# General_IO.net
KiCad netlist of a schematic drawn in EAGLE
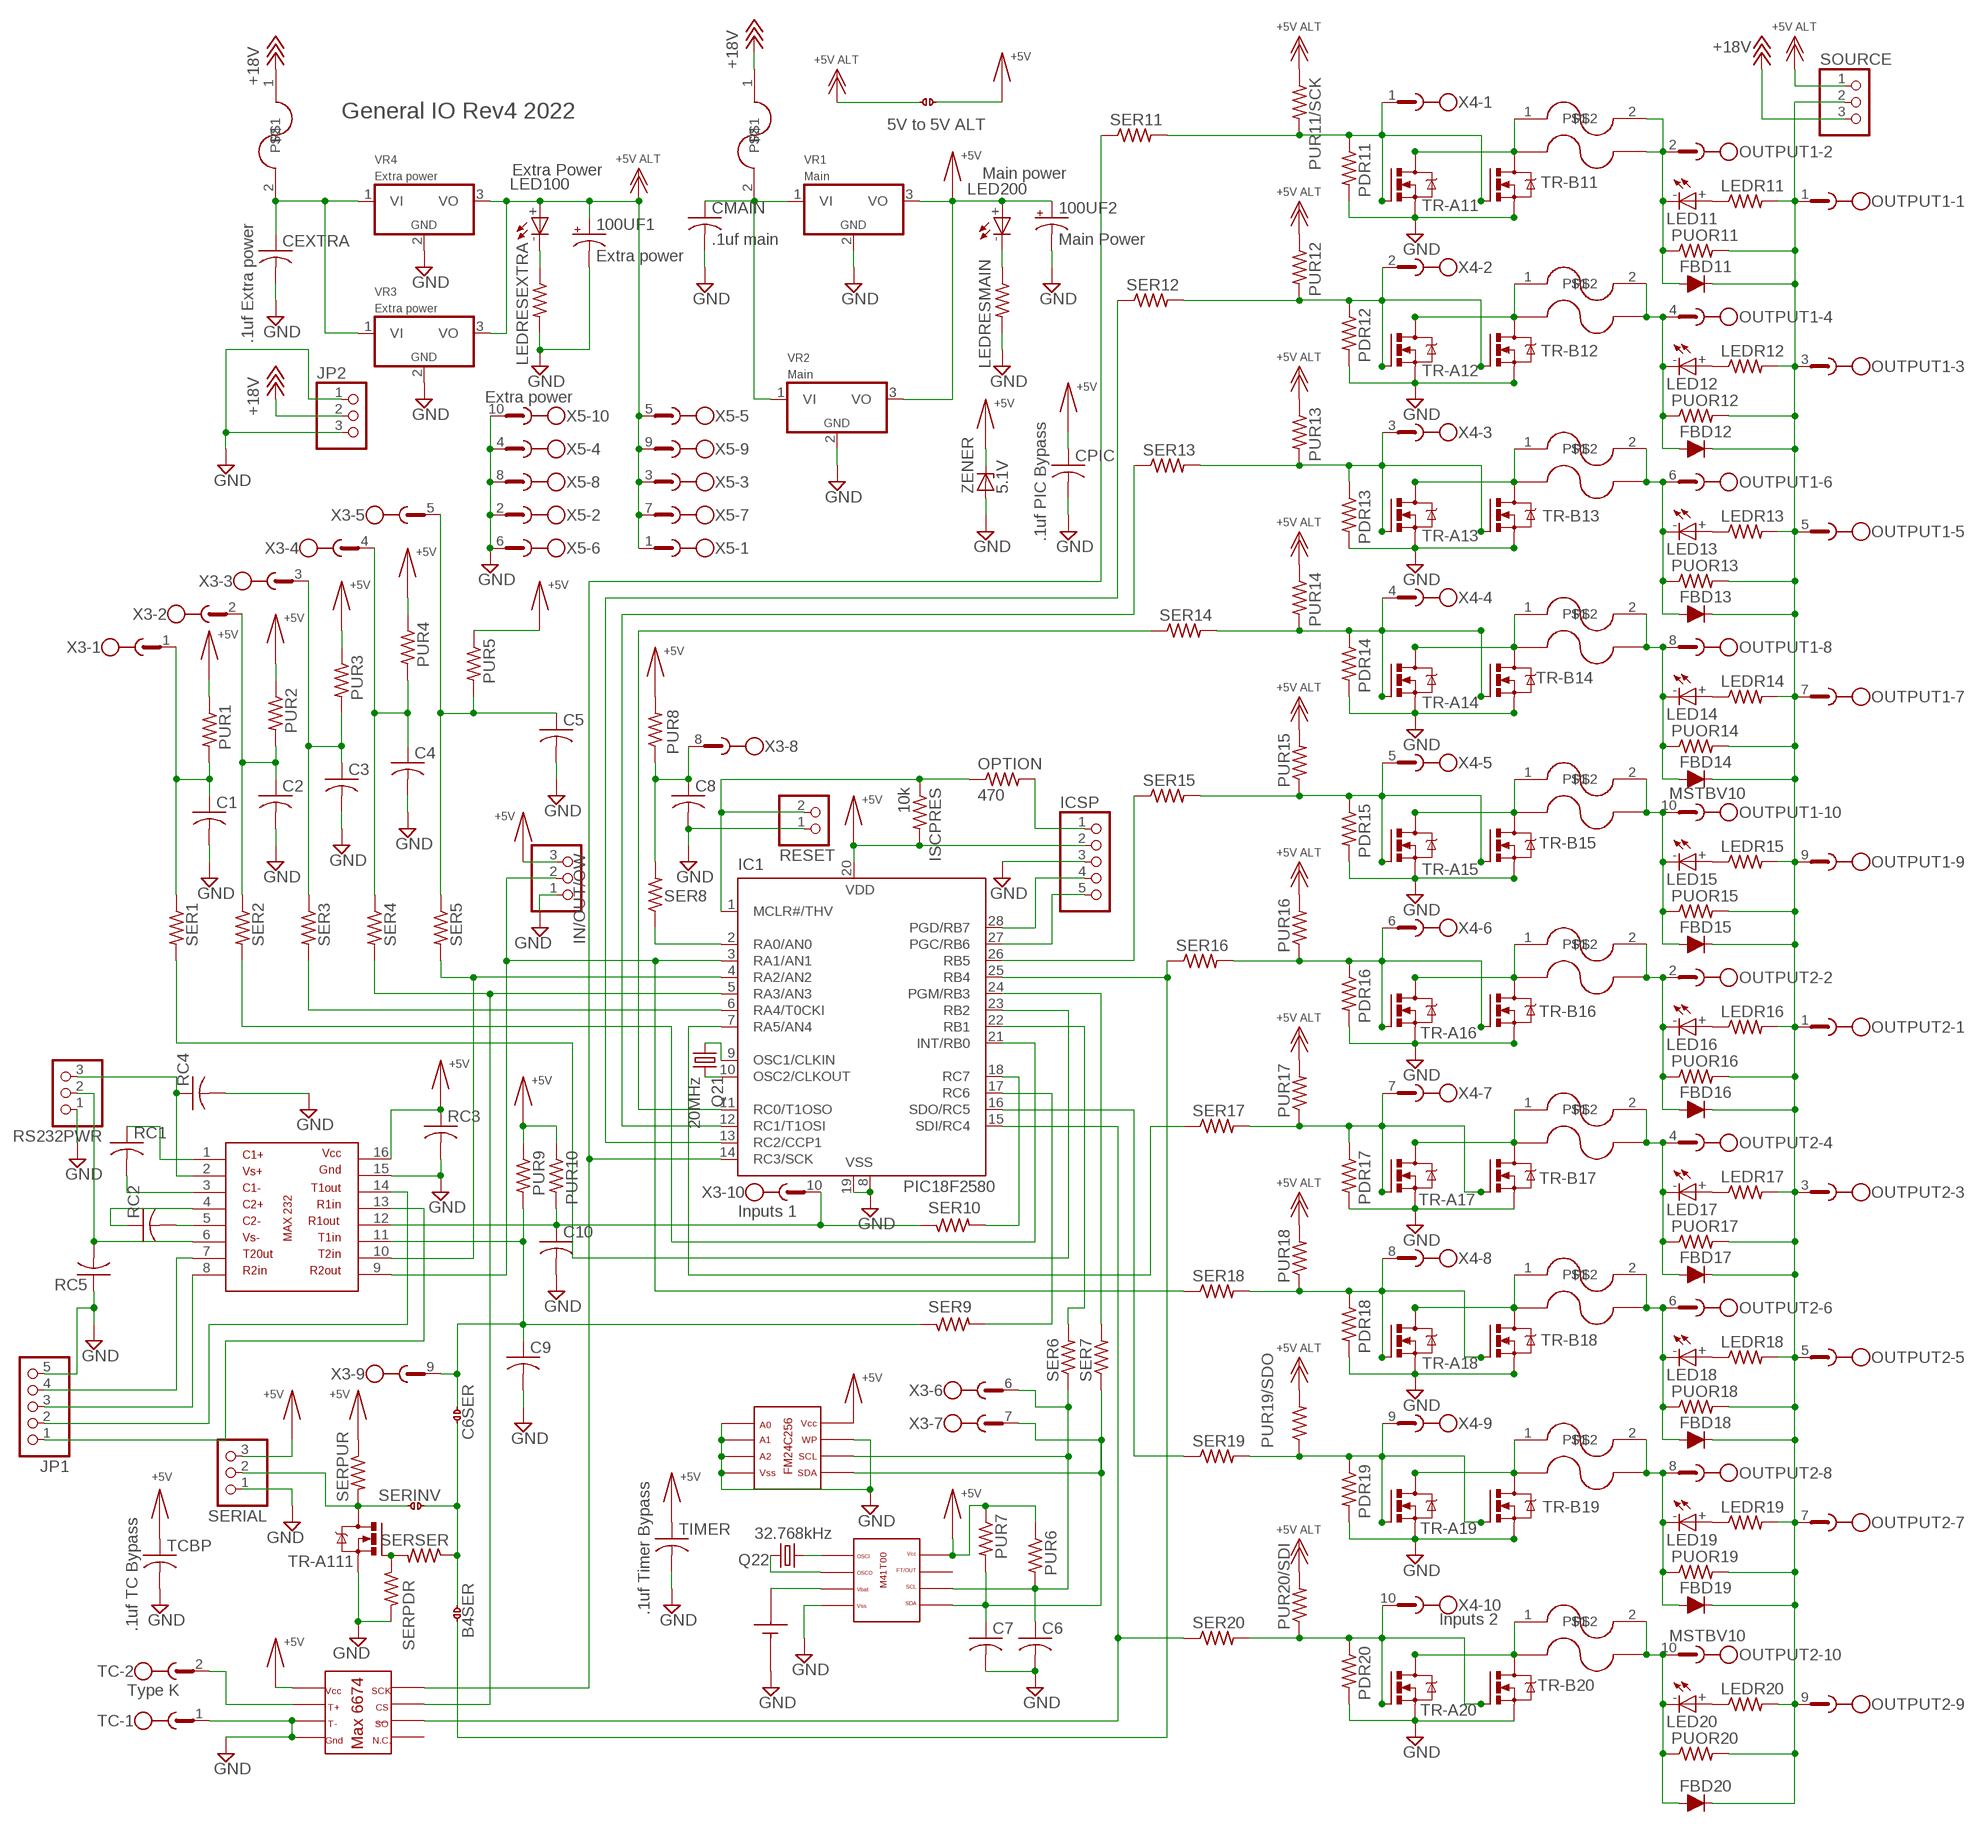
[diagram p0: schematic, sheet 1]

(export (version "E")
  (design (tool "Eeschema 10.0.6"))
  (components
    (comp (ref "100UF1")
      (value "Extra power")
      (footprint "eagle-import:PANASONIC_G")
      (libsource (lib "eagle-import") (part "CAPACITOR-ELECTROLYTICG"))
    )
    (comp (ref "100UF2")
      (value "Main Power")
      (footprint "eagle-import:PANASONIC_G")
      (libsource (lib "eagle-import") (part "CAPACITOR-ELECTROLYTICG"))
    )
    (comp (ref "BAT1")
      (value "BH-401")
      (footprint "eagle-import:BH-401")
      (libsource (lib "eagle-import") (part "BH-401"))
    )
    (comp (ref "C1")
      (value "CAPACITOR-NO-POLARITYC1210")
      (footprint "eagle-import:C1210")
      (libsource (lib "eagle-import") (part "CAPACITOR-NO-POLARITYC1210"))
    )
    (comp (ref "C2")
      (value "CAPACITOR-NO-POLARITYC1210")
      (footprint "eagle-import:C1210")
      (libsource (lib "eagle-import") (part "CAPACITOR-NO-POLARITYC1210"))
    )
    (comp (ref "C3")
      (value "CAPACITOR-NO-POLARITYC1210")
      (footprint "eagle-import:C1210")
      (libsource (lib "eagle-import") (part "CAPACITOR-NO-POLARITYC1210"))
    )
    (comp (ref "C4")
      (value "CAPACITOR-NO-POLARITYC1210")
      (footprint "eagle-import:C1210")
      (libsource (lib "eagle-import") (part "CAPACITOR-NO-POLARITYC1210"))
    )
    (comp (ref "C5")
      (value "CAPACITOR-NO-POLARITYC1210")
      (footprint "eagle-import:C1210")
      (libsource (lib "eagle-import") (part "CAPACITOR-NO-POLARITYC1210"))
    )
    (comp (ref "C6")
      (value "CAPACITOR-NO-POLARITYC1210")
      (footprint "eagle-import:C1210")
      (libsource (lib "eagle-import") (part "CAPACITOR-NO-POLARITYC1210"))
    )
    (comp (ref "C6SER")
      (value "SPLIT_PAD")
      (footprint "eagle-import:SPLIT_PAD")
      (libsource (lib "eagle-import") (part "SPLIT_PAD"))
    )
    (comp (ref "C7")
      (value "CAPACITOR-NO-POLARITYC1210")
      (footprint "eagle-import:C1210")
      (libsource (lib "eagle-import") (part "CAPACITOR-NO-POLARITYC1210"))
    )
    (comp (ref "C8")
      (value "CAPACITOR-NO-POLARITYC1210")
      (footprint "eagle-import:C1210")
      (libsource (lib "eagle-import") (part "CAPACITOR-NO-POLARITYC1210"))
    )
    (comp (ref "C9")
      (value "CAPACITOR-NO-POLARITYC1210")
      (footprint "eagle-import:C1210")
      (libsource (lib "eagle-import") (part "CAPACITOR-NO-POLARITYC1210"))
    )
    (comp (ref "C10")
      (value "CAPACITOR-NO-POLARITYC1210")
      (footprint "eagle-import:C1210")
      (libsource (lib "eagle-import") (part "CAPACITOR-NO-POLARITYC1210"))
    )
    (comp (ref "CEXTRA")
      (value ".1uf Extra power")
      (footprint "eagle-import:C1210")
      (libsource (lib "eagle-import") (part "CAPACITOR-NO-POLARITYC1210"))
    )
    (comp (ref "CMAIN")
      (value ".1uf main")
      (footprint "eagle-import:C1210")
      (libsource (lib "eagle-import") (part "CAPACITOR-NO-POLARITYC1210"))
    )
    (comp (ref "CPIC")
      (value ".1uf PIC Bypass")
      (footprint "eagle-import:C1210")
      (libsource (lib "eagle-import") (part "CAPACITOR-NO-POLARITYC1210"))
    )
    (comp (ref "FBD11")
      (value "D-FILL-SOD-87")
      (footprint "eagle-import:SOD87")
      (libsource (lib "eagle-import") (part "D-FILL-SOD-87"))
    )
    (comp (ref "FBD12")
      (value "D-FILL-SOD-87")
      (footprint "eagle-import:SOD87")
      (libsource (lib "eagle-import") (part "D-FILL-SOD-87"))
    )
    (comp (ref "FBD13")
      (value "D-FILL-SOD-87")
      (footprint "eagle-import:SOD87")
      (libsource (lib "eagle-import") (part "D-FILL-SOD-87"))
    )
    (comp (ref "FBD14")
      (value "D-FILL-SOD-87")
      (footprint "eagle-import:SOD87")
      (libsource (lib "eagle-import") (part "D-FILL-SOD-87"))
    )
    (comp (ref "FBD15")
      (value "D-FILL-SOD-87")
      (footprint "eagle-import:SOD87")
      (libsource (lib "eagle-import") (part "D-FILL-SOD-87"))
    )
    (comp (ref "FBD16")
      (value "D-FILL-SOD-87")
      (footprint "eagle-import:SOD87")
      (libsource (lib "eagle-import") (part "D-FILL-SOD-87"))
    )
    (comp (ref "FBD17")
      (value "D-FILL-SOD-87")
      (footprint "eagle-import:SOD87")
      (libsource (lib "eagle-import") (part "D-FILL-SOD-87"))
    )
    (comp (ref "FBD18")
      (value "D-FILL-SOD-87")
      (footprint "eagle-import:SOD87")
      (libsource (lib "eagle-import") (part "D-FILL-SOD-87"))
    )
    (comp (ref "FBD19")
      (value "D-FILL-SOD-87")
      (footprint "eagle-import:SOD87")
      (libsource (lib "eagle-import") (part "D-FILL-SOD-87"))
    )
    (comp (ref "FBD20")
      (value "D-FILL-SOD-87")
      (footprint "eagle-import:SOD87")
      (libsource (lib "eagle-import") (part "D-FILL-SOD-87"))
    )
    (comp (ref "FUSE9")
      (value "FUSE(SM)")
      (footprint "eagle-import:FUSE")
      (libsource (lib "eagle-import") (part "FUSE(SM)"))
    )
    (comp (ref "FUSE11")
      (value "FUSE(SM)")
      (footprint "eagle-import:FUSE")
      (libsource (lib "eagle-import") (part "FUSE(SM)"))
    )
    (comp (ref "FUSE12")
      (value "FUSE(SM)")
      (footprint "eagle-import:FUSE")
      (libsource (lib "eagle-import") (part "FUSE(SM)"))
    )
    (comp (ref "FUSE13")
      (value "FUSE(SM)")
      (footprint "eagle-import:FUSE")
      (libsource (lib "eagle-import") (part "FUSE(SM)"))
    )
    (comp (ref "FUSE14")
      (value "FUSE(SM)")
      (footprint "eagle-import:FUSE")
      (libsource (lib "eagle-import") (part "FUSE(SM)"))
    )
    (comp (ref "FUSE15")
      (value "FUSE(SM)")
      (footprint "eagle-import:FUSE")
      (libsource (lib "eagle-import") (part "FUSE(SM)"))
    )
    (comp (ref "FUSE16")
      (value "FUSE(SM)")
      (footprint "eagle-import:FUSE")
      (libsource (lib "eagle-import") (part "FUSE(SM)"))
    )
    (comp (ref "FUSE17")
      (value "FUSE(SM)")
      (footprint "eagle-import:FUSE")
      (libsource (lib "eagle-import") (part "FUSE(SM)"))
    )
    (comp (ref "FUSE18")
      (value "FUSE(SM)")
      (footprint "eagle-import:FUSE")
      (libsource (lib "eagle-import") (part "FUSE(SM)"))
    )
    (comp (ref "FUSE20")
      (value "FUSE(SM)")
      (footprint "eagle-import:FUSE")
      (libsource (lib "eagle-import") (part "FUSE(SM)"))
    )
    (comp (ref "IC1")
      (value "PIC18F2580")
      (footprint "eagle-import:SO-28W")
      (libsource (lib "eagle-import") (part "PIC16876SOF"))
    )
    (comp (ref "ICSP")
      (value "PINHD-1X5")
      (footprint "eagle-import:1X05")
      (libsource (lib "eagle-import") (part "PINHD-1X5"))
    )
    (comp (ref "IN/OUT/OW")
      (value "PINHD-1X3")
      (footprint "eagle-import:1X03")
      (libsource (lib "eagle-import") (part "PINHD-1X3"))
    )
    (comp (ref "ISCPRES")
      (value "10k")
      (footprint "eagle-import:M1406")
      (libsource (lib "eagle-import") (part "RESISITORM1406"))
    )
    (comp (ref "JP1")
      (value "PINHD-1X5")
      (footprint "eagle-import:1X05")
      (libsource (lib "eagle-import") (part "PINHD-1X5"))
    )
    (comp (ref "JP2")
      (value "PINHD-1X3")
      (footprint "eagle-import:1X03")
      (libsource (lib "eagle-import") (part "PINHD-1X3"))
    )
    (comp (ref "LED11")
      (value "LED")
      (footprint "eagle-import:1206")
      (libsource (lib "eagle-import") (part "LED"))
    )
    (comp (ref "LED12")
      (value "LED")
      (footprint "eagle-import:1206")
      (libsource (lib "eagle-import") (part "LED"))
    )
    (comp (ref "LED13")
      (value "LED")
      (footprint "eagle-import:1206")
      (libsource (lib "eagle-import") (part "LED"))
    )
    (comp (ref "LED14")
      (value "LED")
      (footprint "eagle-import:1206")
      (libsource (lib "eagle-import") (part "LED"))
    )
    (comp (ref "LED15")
      (value "LED")
      (footprint "eagle-import:1206")
      (libsource (lib "eagle-import") (part "LED"))
    )
    (comp (ref "LED16")
      (value "LED")
      (footprint "eagle-import:1206")
      (libsource (lib "eagle-import") (part "LED"))
    )
    (comp (ref "LED17")
      (value "LED")
      (footprint "eagle-import:1206")
      (libsource (lib "eagle-import") (part "LED"))
    )
    (comp (ref "LED18")
      (value "LED")
      (footprint "eagle-import:1206")
      (libsource (lib "eagle-import") (part "LED"))
    )
    (comp (ref "LED19")
      (value "LED")
      (footprint "eagle-import:1206")
      (libsource (lib "eagle-import") (part "LED"))
    )
    (comp (ref "LED20")
      (value "LED")
      (footprint "eagle-import:1206")
      (libsource (lib "eagle-import") (part "LED"))
    )
    (comp (ref "LED100")
      (value "Extra Power")
      (footprint "eagle-import:1206")
      (libsource (lib "eagle-import") (part "LED"))
    )
    (comp (ref "LED200")
      (value "Main power")
      (footprint "eagle-import:1206")
      (libsource (lib "eagle-import") (part "LED"))
    )
    (comp (ref "LEDR11")
      (value "RESISITORM1406")
      (footprint "eagle-import:M1406")
      (libsource (lib "eagle-import") (part "RESISITORM1406"))
    )
    (comp (ref "LEDR12")
      (value "RESISITORM1406")
      (footprint "eagle-import:M1406")
      (libsource (lib "eagle-import") (part "RESISITORM1406"))
    )
    (comp (ref "LEDR13")
      (value "RESISITORM1406")
      (footprint "eagle-import:M1406")
      (libsource (lib "eagle-import") (part "RESISITORM1406"))
    )
    (comp (ref "LEDR14")
      (value "RESISITORM1406")
      (footprint "eagle-import:M1406")
      (libsource (lib "eagle-import") (part "RESISITORM1406"))
    )
    (comp (ref "LEDR15")
      (value "RESISITORM1406")
      (footprint "eagle-import:M1406")
      (libsource (lib "eagle-import") (part "RESISITORM1406"))
    )
    (comp (ref "LEDR16")
      (value "RESISITORM1406")
      (footprint "eagle-import:M1406")
      (libsource (lib "eagle-import") (part "RESISITORM1406"))
    )
    (comp (ref "LEDR17")
      (value "RESISITORM1406")
      (footprint "eagle-import:M1406")
      (libsource (lib "eagle-import") (part "RESISITORM1406"))
    )
    (comp (ref "LEDR18")
      (value "RESISITORM1406")
      (footprint "eagle-import:M1406")
      (libsource (lib "eagle-import") (part "RESISITORM1406"))
    )
    (comp (ref "LEDR19")
      (value "RESISITORM1406")
      (footprint "eagle-import:M1406")
      (libsource (lib "eagle-import") (part "RESISITORM1406"))
    )
    (comp (ref "LEDR20")
      (value "RESISITORM1406")
      (footprint "eagle-import:M1406")
      (libsource (lib "eagle-import") (part "RESISITORM1406"))
    )
    (comp (ref "LEDRESEXTRA")
      (value "RESISITORR1210")
      (footprint "eagle-import:R1210")
      (libsource (lib "eagle-import") (part "RESISITORR1210"))
    )
    (comp (ref "LEDRESMAIN")
      (value "RESISITORR1210")
      (footprint "eagle-import:R1210")
      (libsource (lib "eagle-import") (part "RESISITORR1210"))
    )
    (comp (ref "OPTION")
      (value "470")
      (footprint "eagle-import:M1406")
      (libsource (lib "eagle-import") (part "RESISITORM1406"))
    )
    (comp (ref "OUTPUT1")
      (value "MSTBV10")
      (footprint "eagle-import:MSTBV10")
      (libsource (lib "eagle-import") (part "MSTBV10"))
    )
    (comp (ref "OUTPUT2")
      (value "MSTBV10")
      (footprint "eagle-import:MSTBV10")
      (libsource (lib "eagle-import") (part "MSTBV10"))
    )
    (comp (ref "PDR11")
      (value "RESISITORM1406")
      (footprint "eagle-import:M1406")
      (libsource (lib "eagle-import") (part "RESISITORM1406"))
    )
    (comp (ref "PDR12")
      (value "RESISITORM1406")
      (footprint "eagle-import:M1406")
      (libsource (lib "eagle-import") (part "RESISITORM1406"))
    )
    (comp (ref "PDR13")
      (value "RESISITORM1406")
      (footprint "eagle-import:M1406")
      (libsource (lib "eagle-import") (part "RESISITORM1406"))
    )
    (comp (ref "PDR14")
      (value "RESISITORM1406")
      (footprint "eagle-import:M1406")
      (libsource (lib "eagle-import") (part "RESISITORM1406"))
    )
    (comp (ref "PDR15")
      (value "RESISITORM1406")
      (footprint "eagle-import:M1406")
      (libsource (lib "eagle-import") (part "RESISITORM1406"))
    )
    (comp (ref "PDR16")
      (value "RESISITORM1406")
      (footprint "eagle-import:M1406")
      (libsource (lib "eagle-import") (part "RESISITORM1406"))
    )
    (comp (ref "PDR17")
      (value "RESISITORM1406")
      (footprint "eagle-import:M1406")
      (libsource (lib "eagle-import") (part "RESISITORM1406"))
    )
    (comp (ref "PDR18")
      (value "RESISITORM1406")
      (footprint "eagle-import:M1406")
      (libsource (lib "eagle-import") (part "RESISITORM1406"))
    )
    (comp (ref "PDR19")
      (value "RESISITORM1406")
      (footprint "eagle-import:M1406")
      (libsource (lib "eagle-import") (part "RESISITORM1406"))
    )
    (comp (ref "PDR20")
      (value "RESISITORM1406")
      (footprint "eagle-import:M1406")
      (libsource (lib "eagle-import") (part "RESISITORM1406"))
    )
    (comp (ref "POLYFUSE11")
      (value "POLYFUSE")
      (footprint "eagle-import:0204_5")
      (libsource (lib "eagle-import") (part "POLYFUSE"))
    )
    (comp (ref "POLYFUSE12")
      (value "POLYFUSE")
      (footprint "eagle-import:0204_5")
      (libsource (lib "eagle-import") (part "POLYFUSE"))
    )
    (comp (ref "POLYFUSE13")
      (value "POLYFUSE")
      (footprint "eagle-import:0204_5")
      (libsource (lib "eagle-import") (part "POLYFUSE"))
    )
    (comp (ref "POLYFUSE14")
      (value "POLYFUSE")
      (footprint "eagle-import:0204_5")
      (libsource (lib "eagle-import") (part "POLYFUSE"))
    )
    (comp (ref "POLYFUSE15")
      (value "POLYFUSE")
      (footprint "eagle-import:0204_5")
      (libsource (lib "eagle-import") (part "POLYFUSE"))
    )
    (comp (ref "POLYFUSE16")
      (value "POLYFUSE")
      (footprint "eagle-import:0204_5")
      (libsource (lib "eagle-import") (part "POLYFUSE"))
    )
    (comp (ref "POLYFUSE17")
      (value "POLYFUSE")
      (footprint "eagle-import:0204_5")
      (libsource (lib "eagle-import") (part "POLYFUSE"))
    )
    (comp (ref "POLYFUSE18")
      (value "POLYFUSE")
      (footprint "eagle-import:0204_5")
      (libsource (lib "eagle-import") (part "POLYFUSE"))
    )
    (comp (ref "POLYFUSE19")
      (value "POLYFUSE")
      (footprint "eagle-import:0204_5")
      (libsource (lib "eagle-import") (part "POLYFUSE"))
    )
    (comp (ref "POLYFUSE20")
      (value "POLYFUSE")
      (footprint "eagle-import:0204_5")
      (libsource (lib "eagle-import") (part "POLYFUSE"))
    )
    (comp (ref "POLYFUSE100")
      (value "Extra Power")
      (footprint "eagle-import:0204_5")
      (libsource (lib "eagle-import") (part "POLYFUSE"))
    )
    (comp (ref "POLYFUSE200")
      (value "Main power")
      (footprint "eagle-import:0204_5")
      (libsource (lib "eagle-import") (part "POLYFUSE"))
    )
    (comp (ref "PUOR11")
      (value "RESISITORM1406")
      (footprint "eagle-import:M1406")
      (libsource (lib "eagle-import") (part "RESISITORM1406"))
    )
    (comp (ref "PUOR12")
      (value "RESISITORM1406")
      (footprint "eagle-import:M1406")
      (libsource (lib "eagle-import") (part "RESISITORM1406"))
    )
    (comp (ref "PUOR13")
      (value "RESISITORM1406")
      (footprint "eagle-import:M1406")
      (libsource (lib "eagle-import") (part "RESISITORM1406"))
    )
    (comp (ref "PUOR14")
      (value "RESISITORM1406")
      (footprint "eagle-import:M1406")
      (libsource (lib "eagle-import") (part "RESISITORM1406"))
    )
    (comp (ref "PUOR15")
      (value "RESISITORM1406")
      (footprint "eagle-import:M1406")
      (libsource (lib "eagle-import") (part "RESISITORM1406"))
    )
    (comp (ref "PUOR16")
      (value "RESISITORM1406")
      (footprint "eagle-import:M1406")
      (libsource (lib "eagle-import") (part "RESISITORM1406"))
    )
    (comp (ref "PUOR17")
      (value "RESISITORM1406")
      (footprint "eagle-import:M1406")
      (libsource (lib "eagle-import") (part "RESISITORM1406"))
    )
    (comp (ref "PUOR18")
      (value "RESISITORM1406")
      (footprint "eagle-import:M1406")
      (libsource (lib "eagle-import") (part "RESISITORM1406"))
    )
    (comp (ref "PUOR19")
      (value "RESISITORM1406")
      (footprint "eagle-import:M1406")
      (libsource (lib "eagle-import") (part "RESISITORM1406"))
    )
    (comp (ref "PUOR20")
      (value "RESISITORM1406")
      (footprint "eagle-import:M1406")
      (libsource (lib "eagle-import") (part "RESISITORM1406"))
    )
    (comp (ref "PUR1")
      (value "RESISITORM1406")
      (footprint "eagle-import:M1406")
      (libsource (lib "eagle-import") (part "RESISITORM1406"))
    )
    (comp (ref "PUR2")
      (value "RESISITORM1406")
      (footprint "eagle-import:M1406")
      (libsource (lib "eagle-import") (part "RESISITORM1406"))
    )
    (comp (ref "PUR3")
      (value "RESISITORM1406")
      (footprint "eagle-import:M1406")
      (libsource (lib "eagle-import") (part "RESISITORM1406"))
    )
    (comp (ref "PUR4")
      (value "RESISITORM1406")
      (footprint "eagle-import:M1406")
      (libsource (lib "eagle-import") (part "RESISITORM1406"))
    )
    (comp (ref "PUR5")
      (value "RESISITORM1406")
      (footprint "eagle-import:M1406")
      (libsource (lib "eagle-import") (part "RESISITORM1406"))
    )
    (comp (ref "PUR6")
      (value "RESISITORM1406")
      (footprint "eagle-import:M1406")
      (libsource (lib "eagle-import") (part "RESISITORM1406"))
    )
    (comp (ref "PUR7")
      (value "RESISITORM1406")
      (footprint "eagle-import:M1406")
      (libsource (lib "eagle-import") (part "RESISITORM1406"))
    )
    (comp (ref "PUR8")
      (value "RESISITORM1406")
      (footprint "eagle-import:M1406")
      (libsource (lib "eagle-import") (part "RESISITORM1406"))
    )
    (comp (ref "PUR9")
      (value "RESISITORM1406")
      (footprint "eagle-import:M1406")
      (libsource (lib "eagle-import") (part "RESISITORM1406"))
    )
    (comp (ref "PUR10")
      (value "RESISITORM1406")
      (footprint "eagle-import:M1406")
      (libsource (lib "eagle-import") (part "RESISITORM1406"))
    )
    (comp (ref "PUR11/SCK")
      (value "RESISITORM1406")
      (footprint "eagle-import:M1406")
      (libsource (lib "eagle-import") (part "RESISITORM1406"))
    )
    (comp (ref "PUR12")
      (value "RESISITORM1406")
      (footprint "eagle-import:M1406")
      (libsource (lib "eagle-import") (part "RESISITORM1406"))
    )
    (comp (ref "PUR13")
      (value "RESISITORM1406")
      (footprint "eagle-import:M1406")
      (libsource (lib "eagle-import") (part "RESISITORM1406"))
    )
    (comp (ref "PUR14")
      (value "RESISITORM1406")
      (footprint "eagle-import:M1406")
      (libsource (lib "eagle-import") (part "RESISITORM1406"))
    )
    (comp (ref "PUR15")
      (value "RESISITORM1406")
      (footprint "eagle-import:M1406")
      (libsource (lib "eagle-import") (part "RESISITORM1406"))
    )
    (comp (ref "PUR16")
      (value "RESISITORM1406")
      (footprint "eagle-import:M1406")
      (libsource (lib "eagle-import") (part "RESISITORM1406"))
    )
    (comp (ref "PUR17")
      (value "RESISITORM1406")
      (footprint "eagle-import:M1406")
      (libsource (lib "eagle-import") (part "RESISITORM1406"))
    )
    (comp (ref "PUR18")
      (value "RESISITORM1406")
      (footprint "eagle-import:M1406")
      (libsource (lib "eagle-import") (part "RESISITORM1406"))
    )
    (comp (ref "PUR19/SDO")
      (value "RESISITORM1406")
      (footprint "eagle-import:M1406")
      (libsource (lib "eagle-import") (part "RESISITORM1406"))
    )
    (comp (ref "PUR20/SDI")
      (value "RESISITORM1406")
      (footprint "eagle-import:M1406")
      (libsource (lib "eagle-import") (part "RESISITORM1406"))
    )
    (comp (ref "Q21")
      (value "20MHz")
      (footprint "eagle-import:SM49")
      (libsource (lib "eagle-import") (part "CRYSTALSM49"))
    )
    (comp (ref "Q22")
      (value "32.768kHz")
      (footprint "eagle-import:TC26H")
      (libsource (lib "eagle-import") (part "CRYSTALTC26H"))
    )
    (comp (ref "RC1")
      (value "CAPACITOR-NO-POLARITYC1210")
      (footprint "eagle-import:C1210")
      (libsource (lib "eagle-import") (part "CAPACITOR-NO-POLARITYC1210"))
    )
    (comp (ref "RC2")
      (value "CAPACITOR-NO-POLARITYC1210")
      (footprint "eagle-import:C1210")
      (libsource (lib "eagle-import") (part "CAPACITOR-NO-POLARITYC1210"))
    )
    (comp (ref "RC3")
      (value "CAPACITOR-NO-POLARITYC1210")
      (footprint "eagle-import:C1210")
      (libsource (lib "eagle-import") (part "CAPACITOR-NO-POLARITYC1210"))
    )
    (comp (ref "RC4")
      (value "CAPACITOR-NO-POLARITYC1210")
      (footprint "eagle-import:C1210")
      (libsource (lib "eagle-import") (part "CAPACITOR-NO-POLARITYC1210"))
    )
    (comp (ref "RC5")
      (value "CAPACITOR-NO-POLARITYC1210")
      (footprint "eagle-import:C1210")
      (libsource (lib "eagle-import") (part "CAPACITOR-NO-POLARITYC1210"))
    )
    (comp (ref "RESET")
      (value "PINHD-1X2")
      (footprint "eagle-import:1X02")
      (libsource (lib "eagle-import") (part "PINHD-1X2"))
    )
    (comp (ref "RS232PWR")
      (value "PINHD-1X3")
      (footprint "eagle-import:1X03")
      (libsource (lib "eagle-import") (part "PINHD-1X3"))
    )
    (comp (ref "SER1")
      (value "RESISITORM1406")
      (footprint "eagle-import:M1406")
      (libsource (lib "eagle-import") (part "RESISITORM1406"))
    )
    (comp (ref "SER2")
      (value "RESISITORM1406")
      (footprint "eagle-import:M1406")
      (libsource (lib "eagle-import") (part "RESISITORM1406"))
    )
    (comp (ref "SER3")
      (value "RESISITORM1406")
      (footprint "eagle-import:M1406")
      (libsource (lib "eagle-import") (part "RESISITORM1406"))
    )
    (comp (ref "SER4")
      (value "RESISITORM1406")
      (footprint "eagle-import:M1406")
      (libsource (lib "eagle-import") (part "RESISITORM1406"))
    )
    (comp (ref "SER5")
      (value "RESISITORM1406")
      (footprint "eagle-import:M1406")
      (libsource (lib "eagle-import") (part "RESISITORM1406"))
    )
    (comp (ref "SER6")
      (value "RESISITORM1406")
      (footprint "eagle-import:M1406")
      (libsource (lib "eagle-import") (part "RESISITORM1406"))
    )
    (comp (ref "SER7")
      (value "RESISITORM1406")
      (footprint "eagle-import:M1406")
      (libsource (lib "eagle-import") (part "RESISITORM1406"))
    )
    (comp (ref "SER8")
      (value "RESISITORM1406")
      (footprint "eagle-import:M1406")
      (libsource (lib "eagle-import") (part "RESISITORM1406"))
    )
    (comp (ref "SER9")
      (value "RESISITORM1406")
      (footprint "eagle-import:M1406")
      (libsource (lib "eagle-import") (part "RESISITORM1406"))
    )
    (comp (ref "SER10")
      (value "RESISITORM1406")
      (footprint "eagle-import:M1406")
      (libsource (lib "eagle-import") (part "RESISITORM1406"))
    )
    (comp (ref "SER11")
      (value "RESISITORM1406")
      (footprint "eagle-import:M1406")
      (libsource (lib "eagle-import") (part "RESISITORM1406"))
    )
    (comp (ref "SER12")
      (value "RESISITORM1406")
      (footprint "eagle-import:M1406")
      (libsource (lib "eagle-import") (part "RESISITORM1406"))
    )
    (comp (ref "SER13")
      (value "RESISITORM1406")
      (footprint "eagle-import:M1406")
      (libsource (lib "eagle-import") (part "RESISITORM1406"))
    )
    (comp (ref "SER14")
      (value "RESISITORM1406")
      (footprint "eagle-import:M1406")
      (libsource (lib "eagle-import") (part "RESISITORM1406"))
    )
    (comp (ref "SER15")
      (value "RESISITORM1406")
      (footprint "eagle-import:M1406")
      (libsource (lib "eagle-import") (part "RESISITORM1406"))
    )
    (comp (ref "SER16")
      (value "RESISITORM1406")
      (footprint "eagle-import:M1406")
      (libsource (lib "eagle-import") (part "RESISITORM1406"))
    )
    (comp (ref "SER17")
      (value "RESISITORM1406")
      (footprint "eagle-import:M1406")
      (libsource (lib "eagle-import") (part "RESISITORM1406"))
    )
    (comp (ref "SER18")
      (value "RESISITORM1406")
      (footprint "eagle-import:M1406")
      (libsource (lib "eagle-import") (part "RESISITORM1406"))
    )
    (comp (ref "SER19")
      (value "RESISITORM1406")
      (footprint "eagle-import:M1406")
      (libsource (lib "eagle-import") (part "RESISITORM1406"))
    )
    (comp (ref "SER20")
      (value "RESISITORM1406")
      (footprint "eagle-import:M1406")
      (libsource (lib "eagle-import") (part "RESISITORM1406"))
    )
    (comp (ref "SERIAL")
      (value "PINHD-1X3")
      (footprint "eagle-import:1X03")
      (libsource (lib "eagle-import") (part "PINHD-1X3"))
    )
    (comp (ref "SERPDR")
      (value "RESISITORM1406")
      (footprint "eagle-import:M1406")
      (libsource (lib "eagle-import") (part "RESISITORM1406"))
    )
    (comp (ref "SERPUR")
      (value "RESISITORM1406")
      (footprint "eagle-import:M1406")
      (libsource (lib "eagle-import") (part "RESISITORM1406"))
    )
    (comp (ref "SERSER")
      (value "RESISITORM1406")
      (footprint "eagle-import:M1406")
      (libsource (lib "eagle-import") (part "RESISITORM1406"))
    )
    (comp (ref "SOURCE")
      (value "PINHD-1X3")
      (footprint "eagle-import:1X03")
      (libsource (lib "eagle-import") (part "PINHD-1X3"))
    )
    (comp (ref "TC")
      (value "Type K")
      (footprint "eagle-import:MSTBV2")
      (libsource (lib "eagle-import") (part "MST2V"))
    )
    (comp (ref "TCBP")
      (value ".1uf TC Bypass")
      (footprint "eagle-import:C1210")
      (libsource (lib "eagle-import") (part "CAPACITOR-NO-POLARITYC1210"))
    )
    (comp (ref "TIMER")
      (value ".1uf Timer Bypass")
      (footprint "eagle-import:C1210")
      (libsource (lib "eagle-import") (part "CAPACITOR-NO-POLARITYC1210"))
    )
    (comp (ref "TR-A11")
      (value "ZXMN10A08GSOT223")
      (footprint "eagle-import:SOT223R_INFINEON")
      (libsource (lib "eagle-import") (part "ZXMN10A08GSOT223"))
    )
    (comp (ref "TR-A12")
      (value "ZXMN10A08GSOT223")
      (footprint "eagle-import:SOT223R_INFINEON")
      (libsource (lib "eagle-import") (part "ZXMN10A08GSOT223"))
    )
    (comp (ref "TR-A13")
      (value "ZXMN10A08GSOT223")
      (footprint "eagle-import:SOT223R_INFINEON")
      (libsource (lib "eagle-import") (part "ZXMN10A08GSOT223"))
    )
    (comp (ref "TR-A14")
      (value "ZXMN10A08GSOT223")
      (footprint "eagle-import:SOT223R_INFINEON")
      (libsource (lib "eagle-import") (part "ZXMN10A08GSOT223"))
    )
    (comp (ref "TR-A15")
      (value "ZXMN10A08GSOT223")
      (footprint "eagle-import:SOT223R_INFINEON")
      (libsource (lib "eagle-import") (part "ZXMN10A08GSOT223"))
    )
    (comp (ref "TR-A16")
      (value "ZXMN10A08GSOT223")
      (footprint "eagle-import:SOT223R_INFINEON")
      (libsource (lib "eagle-import") (part "ZXMN10A08GSOT223"))
    )
    (comp (ref "TR-A17")
      (value "ZXMN10A08GSOT223")
      (footprint "eagle-import:SOT223R_INFINEON")
      (libsource (lib "eagle-import") (part "ZXMN10A08GSOT223"))
    )
    (comp (ref "TR-A18")
      (value "ZXMN10A08GSOT223")
      (footprint "eagle-import:SOT223R_INFINEON")
      (libsource (lib "eagle-import") (part "ZXMN10A08GSOT223"))
    )
    (comp (ref "TR-A19")
      (value "ZXMN10A08GSOT223")
      (footprint "eagle-import:SOT223R_INFINEON")
      (libsource (lib "eagle-import") (part "ZXMN10A08GSOT223"))
    )
    (comp (ref "TR-A20")
      (value "ZXMN10A08GSOT223")
      (footprint "eagle-import:SOT223R_INFINEON")
      (libsource (lib "eagle-import") (part "ZXMN10A08GSOT223"))
    )
    (comp (ref "TR-A111")
      (value "ZXMN10A08GSOT223")
      (footprint "eagle-import:SOT223R_INFINEON")
      (libsource (lib "eagle-import") (part "ZXMN10A08GSOT223"))
    )
    (comp (ref "TR-B11")
      (value "ZXMN10A08G")
      (footprint "eagle-import:TO220BV")
      (libsource (lib "eagle-import") (part "ZXMN10A08G"))
    )
    (comp (ref "TR-B12")
      (value "ZXMN10A08G")
      (footprint "eagle-import:TO220BV")
      (libsource (lib "eagle-import") (part "ZXMN10A08G"))
    )
    (comp (ref "TR-B13")
      (value "ZXMN10A08G")
      (footprint "eagle-import:TO220BV")
      (libsource (lib "eagle-import") (part "ZXMN10A08G"))
    )
    (comp (ref "TR-B14")
      (value "ZXMN10A08G")
      (footprint "eagle-import:TO220BV")
      (libsource (lib "eagle-import") (part "ZXMN10A08G"))
    )
    (comp (ref "TR-B15")
      (value "ZXMN10A08G")
      (footprint "eagle-import:TO220BV")
      (libsource (lib "eagle-import") (part "ZXMN10A08G"))
    )
    (comp (ref "TR-B16")
      (value "ZXMN10A08G")
      (footprint "eagle-import:TO220BV")
      (libsource (lib "eagle-import") (part "ZXMN10A08G"))
    )
    (comp (ref "TR-B17")
      (value "ZXMN10A08G")
      (footprint "eagle-import:TO220BV")
      (libsource (lib "eagle-import") (part "ZXMN10A08G"))
    )
    (comp (ref "TR-B18")
      (value "ZXMN10A08G")
      (footprint "eagle-import:TO220BV")
      (libsource (lib "eagle-import") (part "ZXMN10A08G"))
    )
    (comp (ref "TR-B19")
      (value "ZXMN10A08G")
      (footprint "eagle-import:TO220BV")
      (libsource (lib "eagle-import") (part "ZXMN10A08G"))
    )
    (comp (ref "TR-B20")
      (value "ZXMN10A08G")
      (footprint "eagle-import:TO220BV")
      (libsource (lib "eagle-import") (part "ZXMN10A08G"))
    )
    (comp (ref "U$1")
      (value "MAX232")
      (footprint "eagle-import:SO16")
      (libsource (lib "eagle-import") (part "MAX232"))
    )
    (comp (ref "U$2")
      (value "MAX6674")
      (footprint "eagle-import:SO08")
      (libsource (lib "eagle-import") (part "MAX6674"))
    )
    (comp (ref "U$4")
      (value "M41T00TIMER-I2C")
      (footprint "eagle-import:SO08")
      (libsource (lib "eagle-import") (part "M41T00TIMER-I2C"))
    )
    (comp (ref "U$18")
      (value "FM24C256")
      (footprint "eagle-import:SO08")
      (libsource (lib "eagle-import") (part "FM24C256"))
    )
    (comp (ref "U$21")
      (value "SPLIT_PAD")
      (footprint "eagle-import:SPLIT_PAD")
      (libsource (lib "eagle-import") (part "SPLIT_PAD"))
    )
    (comp (ref "U$23")
      (value "SPLIT_PAD")
      (footprint "eagle-import:SPLIT_PAD")
      (libsource (lib "eagle-import") (part "SPLIT_PAD"))
    )
    (comp (ref "U$24")
      (value "SPLIT_PAD")
      (footprint "eagle-import:SPLIT_PAD")
      (libsource (lib "eagle-import") (part "SPLIT_PAD"))
    )
    (comp (ref "VR1")
      (value "Main")
      (footprint "eagle-import:TO220S")
      (libsource (lib "eagle-import") (part "VOLTAGE-REGULATOR"))
    )
    (comp (ref "VR2")
      (value "Main")
      (footprint "eagle-import:SOT223R_INFINEON")
      (libsource (lib "eagle-import") (part "VOLTAGE-REGULATORSO-223"))
    )
    (comp (ref "VR3")
      (value "Extra power")
      (footprint "eagle-import:SOT223R_INFINEON")
      (libsource (lib "eagle-import") (part "VOLTAGE-REGULATORSO-223"))
    )
    (comp (ref "VR4")
      (value "Extra power")
      (footprint "eagle-import:TO220S")
      (libsource (lib "eagle-import") (part "VOLTAGE-REGULATOR"))
    )
    (comp (ref "X3")
      (value "Inputs 1")
      (footprint "eagle-import:MSTBV10")
      (libsource (lib "eagle-import") (part "MSTBV10"))
    )
    (comp (ref "X4")
      (value "Inputs 2")
      (footprint "eagle-import:MSTBV10")
      (libsource (lib "eagle-import") (part "MSTBV10"))
    )
    (comp (ref "X5")
      (value "Extra power")
      (footprint "eagle-import:MSTBV10")
      (libsource (lib "eagle-import") (part "MSTBV10"))
    )
    (comp (ref "ZENER")
      (value "5.1V")
      (footprint "eagle-import:SMB")
      (libsource (lib "eagle-import") (part "ZENER-DIODESMB"))
    )
  )
  (nets
    (net (code "1") (name "+5V") (class "Default")
      (node (ref "100UF2") (pin "+") (pinfunction "+_+") (pintype "passive"))
      (node (ref "CPIC") (pin "1") (pinfunction "1_1") (pintype "passive"))
      (node (ref "IC1") (pin "20") (pinfunction "VDD_20") (pintype "power_in"))
      (node (ref "ICSP") (pin "2") (pinfunction "2_2") (pintype "passive"))
      (node (ref "IN/OUT/OW") (pin "3") (pinfunction "3_3") (pintype "passive"))
      (node (ref "ISCPRES") (pin "2") (pinfunction "2_2") (pintype "passive"))
      (node (ref "LED200") (pin "+") (pinfunction "+_+") (pintype "passive"))
      (node (ref "PUR1") (pin "1") (pinfunction "1_1") (pintype "passive"))
      (node (ref "PUR10") (pin "1") (pinfunction "1_1") (pintype "passive"))
      (node (ref "PUR2") (pin "1") (pinfunction "1_1") (pintype "passive"))
      (node (ref "PUR3") (pin "1") (pinfunction "1_1") (pintype "passive"))
      (node (ref "PUR4") (pin "1") (pinfunction "1_1") (pintype "passive"))
      (node (ref "PUR5") (pin "1") (pinfunction "1_1") (pintype "passive"))
      (node (ref "PUR6") (pin "1") (pinfunction "1_1") (pintype "passive"))
      (node (ref "PUR7") (pin "1") (pinfunction "1_1") (pintype "passive"))
      (node (ref "PUR8") (pin "2") (pinfunction "2_2") (pintype "passive"))
      (node (ref "PUR9") (pin "1") (pinfunction "1_1") (pintype "passive"))
      (node (ref "RC3") (pin "1") (pinfunction "1_1") (pintype "passive"))
      (node (ref "SERIAL") (pin "3") (pinfunction "3_3") (pintype "passive"))
      (node (ref "SERPUR") (pin "1") (pinfunction "1_1") (pintype "passive"))
      (node (ref "TCBP") (pin "1") (pinfunction "1_1") (pintype "passive"))
      (node (ref "TIMER") (pin "1") (pinfunction "1_1") (pintype "passive"))
      (node (ref "U$1") (pin "16") (pinfunction "P$16_16") (pintype "bidirectional"))
      (node (ref "U$18") (pin "8") (pinfunction "VDD_8") (pintype "bidirectional"))
      (node (ref "U$2") (pin "4") (pinfunction "P$4_4") (pintype "bidirectional"))
      (node (ref "U$21") (pin "P$1") (pinfunction "P$1_P$1") (pintype "bidirectional"))
      (node (ref "U$4") (pin "8") (pinfunction "VCC_8") (pintype "power_in"))
      (node (ref "VR1") (pin "3") (pinfunction "VO_3") (pintype "passive"))
      (node (ref "VR2") (pin "3") (pinfunction "VO_3") (pintype "passive"))
      (node (ref "ZENER") (pin "C") (pinfunction "C_C") (pintype "passive"))
    )
    (net (code "2") (name "+18V") (class "Default")
      (node (ref "JP2") (pin "2") (pinfunction "2_2") (pintype "passive"))
      (node (ref "POLYFUSE100") (pin "1") (pinfunction "P$1_1") (pintype "bidirectional"))
      (node (ref "POLYFUSE200") (pin "1") (pinfunction "P$1_1") (pintype "bidirectional"))
      (node (ref "SOURCE") (pin "3") (pinfunction "3_3") (pintype "passive"))
    )
    (net (code "3") (name "ALT5V") (class "Default")
      (node (ref "100UF1") (pin "+") (pinfunction "+_+") (pintype "passive"))
      (node (ref "LED100") (pin "+") (pinfunction "+_+") (pintype "passive"))
      (node (ref "PUR11/SCK") (pin "1") (pinfunction "1_1") (pintype "passive"))
      (node (ref "PUR12") (pin "1") (pinfunction "1_1") (pintype "passive"))
      (node (ref "PUR13") (pin "1") (pinfunction "1_1") (pintype "passive"))
      (node (ref "PUR14") (pin "1") (pinfunction "1_1") (pintype "passive"))
      (node (ref "PUR15") (pin "2") (pinfunction "2_2") (pintype "passive"))
      (node (ref "PUR16") (pin "2") (pinfunction "2_2") (pintype "passive"))
      (node (ref "PUR17") (pin "2") (pinfunction "2_2") (pintype "passive"))
      (node (ref "PUR18") (pin "2") (pinfunction "2_2") (pintype "passive"))
      (node (ref "PUR19/SDO") (pin "2") (pinfunction "2_2") (pintype "passive"))
      (node (ref "PUR20/SDI") (pin "2") (pinfunction "2_2") (pintype "passive"))
      (node (ref "SOURCE") (pin "1") (pinfunction "1_1") (pintype "passive"))
      (node (ref "U$21") (pin "P$2") (pinfunction "P$2_P$2") (pintype "bidirectional"))
      (node (ref "VR3") (pin "3") (pinfunction "VO_3") (pintype "passive"))
      (node (ref "VR4") (pin "3") (pinfunction "VO_3") (pintype "passive"))
      (node (ref "X5") (pin "1") (pinfunction "1_1") (pintype "passive"))
      (node (ref "X5") (pin "3") (pinfunction "1_3") (pintype "passive"))
      (node (ref "X5") (pin "5") (pinfunction "1_5") (pintype "passive"))
      (node (ref "X5") (pin "7") (pinfunction "1_7") (pintype "passive"))
      (node (ref "X5") (pin "9") (pinfunction "1_9") (pintype "passive"))
    )
    (net (code "4") (name "GND") (class "Default")
      (node (ref "100UF1") (pin "-") (pinfunction "-_-") (pintype "passive"))
      (node (ref "100UF2") (pin "-") (pinfunction "-_-") (pintype "passive"))
      (node (ref "BAT1") (pin "P$2") (pinfunction "P$2_P$2") (pintype "bidirectional"))
      (node (ref "C1") (pin "2") (pinfunction "2_2") (pintype "passive"))
      (node (ref "C10") (pin "2") (pinfunction "2_2") (pintype "passive"))
      (node (ref "C2") (pin "2") (pinfunction "2_2") (pintype "passive"))
      (node (ref "C3") (pin "2") (pinfunction "2_2") (pintype "passive"))
      (node (ref "C4") (pin "2") (pinfunction "2_2") (pintype "passive"))
      (node (ref "C5") (pin "2") (pinfunction "2_2") (pintype "passive"))
      (node (ref "C6") (pin "2") (pinfunction "2_2") (pintype "passive"))
      (node (ref "C7") (pin "2") (pinfunction "2_2") (pintype "passive"))
      (node (ref "C8") (pin "2") (pinfunction "2_2") (pintype "passive"))
      (node (ref "C9") (pin "2") (pinfunction "2_2") (pintype "passive"))
      (node (ref "CEXTRA") (pin "2") (pinfunction "2_2") (pintype "passive"))
      (node (ref "CMAIN") (pin "2") (pinfunction "2_2") (pintype "passive"))
      (node (ref "CPIC") (pin "2") (pinfunction "2_2") (pintype "passive"))
      (node (ref "IC1") (pin "19") (pinfunction "VSS_19") (pintype "power_in"))
      (node (ref "IC1") (pin "8") (pinfunction "VSS_8") (pintype "power_in"))
      (node (ref "ICSP") (pin "3") (pinfunction "3_3") (pintype "passive"))
      (node (ref "IN/OUT/OW") (pin "1") (pinfunction "1_1") (pintype "passive"))
      (node (ref "JP1") (pin "5") (pinfunction "5_5") (pintype "passive"))
      (node (ref "JP2") (pin "1") (pinfunction "1_1") (pintype "passive"))
      (node (ref "JP2") (pin "3") (pinfunction "3_3") (pintype "passive"))
      (node (ref "LEDRESEXTRA") (pin "2") (pinfunction "2_2") (pintype "passive"))
      (node (ref "LEDRESMAIN") (pin "2") (pinfunction "2_2") (pintype "passive"))
      (node (ref "PDR11") (pin "2") (pinfunction "2_2") (pintype "passive"))
      (node (ref "PDR12") (pin "2") (pinfunction "2_2") (pintype "passive"))
      (node (ref "PDR13") (pin "2") (pinfunction "2_2") (pintype "passive"))
      (node (ref "PDR14") (pin "2") (pinfunction "2_2") (pintype "passive"))
      (node (ref "PDR15") (pin "2") (pinfunction "2_2") (pintype "passive"))
      (node (ref "PDR16") (pin "2") (pinfunction "2_2") (pintype "passive"))
      (node (ref "PDR17") (pin "2") (pinfunction "2_2") (pintype "passive"))
      (node (ref "PDR18") (pin "2") (pinfunction "2_2") (pintype "passive"))
      (node (ref "PDR19") (pin "2") (pinfunction "2_2") (pintype "passive"))
      (node (ref "PDR20") (pin "2") (pinfunction "2_2") (pintype "passive"))
      (node (ref "RC3") (pin "2") (pinfunction "2_2") (pintype "passive"))
      (node (ref "RC4") (pin "2") (pinfunction "2_2") (pintype "passive"))
      (node (ref "RC5") (pin "1") (pinfunction "1_1") (pintype "passive"))
      (node (ref "RESET") (pin "1") (pinfunction "1_1") (pintype "passive"))
      (node (ref "RS232PWR") (pin "1") (pinfunction "1_1") (pintype "passive"))
      (node (ref "SERIAL") (pin "1") (pinfunction "1_1") (pintype "passive"))
      (node (ref "SERPDR") (pin "2") (pinfunction "2_2") (pintype "passive"))
      (node (ref "TC") (pin "1") (pinfunction "1_1") (pintype "passive"))
      (node (ref "TCBP") (pin "2") (pinfunction "2_2") (pintype "passive"))
      (node (ref "TIMER") (pin "2") (pinfunction "2_2") (pintype "passive"))
      (node (ref "TR-A11") (pin "3") (pinfunction "S_3") (pintype "passive"))
      (node (ref "TR-A111") (pin "3") (pinfunction "S_3") (pintype "passive"))
      (node (ref "TR-A12") (pin "3") (pinfunction "S_3") (pintype "passive"))
      (node (ref "TR-A13") (pin "3") (pinfunction "S_3") (pintype "passive"))
      (node (ref "TR-A14") (pin "3") (pinfunction "S_3") (pintype "passive"))
      (node (ref "TR-A15") (pin "3") (pinfunction "S_3") (pintype "passive"))
      (node (ref "TR-A16") (pin "3") (pinfunction "S_3") (pintype "passive"))
      (node (ref "TR-A17") (pin "3") (pinfunction "S_3") (pintype "passive"))
      (node (ref "TR-A18") (pin "3") (pinfunction "S_3") (pintype "passive"))
      (node (ref "TR-A19") (pin "3") (pinfunction "S_3") (pintype "passive"))
      (node (ref "TR-A20") (pin "3") (pinfunction "S_3") (pintype "passive"))
      (node (ref "TR-B11") (pin "S") (pinfunction "S_S") (pintype "passive"))
      (node (ref "TR-B12") (pin "S") (pinfunction "S_S") (pintype "passive"))
      (node (ref "TR-B13") (pin "S") (pinfunction "S_S") (pintype "passive"))
      (node (ref "TR-B14") (pin "S") (pinfunction "S_S") (pintype "passive"))
      (node (ref "TR-B15") (pin "S") (pinfunction "S_S") (pintype "passive"))
      (node (ref "TR-B16") (pin "S") (pinfunction "S_S") (pintype "passive"))
      (node (ref "TR-B17") (pin "S") (pinfunction "S_S") (pintype "passive"))
      (node (ref "TR-B18") (pin "S") (pinfunction "S_S") (pintype "passive"))
      (node (ref "TR-B19") (pin "S") (pinfunction "S_S") (pintype "passive"))
      (node (ref "TR-B20") (pin "S") (pinfunction "S_S") (pintype "passive"))
      (node (ref "U$1") (pin "15") (pinfunction "P$15_15") (pintype "bidirectional"))
      (node (ref "U$18") (pin "1") (pinfunction "A0_1") (pintype "bidirectional"))
      (node (ref "U$18") (pin "2") (pinfunction "A1_2") (pintype "bidirectional"))
      (node (ref "U$18") (pin "3") (pinfunction "A2_3") (pintype "bidirectional"))
      (node (ref "U$18") (pin "4") (pinfunction "VSS_4") (pintype "bidirectional"))
      (node (ref "U$18") (pin "7") (pinfunction "WP_7") (pintype "bidirectional"))
      (node (ref "U$2") (pin "1") (pinfunction "P$1_1") (pintype "bidirectional"))
      (node (ref "U$2") (pin "2") (pinfunction "P$2_2") (pintype "bidirectional"))
      (node (ref "U$4") (pin "4") (pinfunction "VSS_4") (pintype "power_in"))
      (node (ref "VR1") (pin "2") (pinfunction "GND_2") (pintype "passive"))
      (node (ref "VR2") (pin "2") (pinfunction "GND_2") (pintype "passive"))
      (node (ref "VR3") (pin "2") (pinfunction "GND_2") (pintype "passive"))
      (node (ref "VR4") (pin "2") (pinfunction "GND_2") (pintype "passive"))
      (node (ref "X5") (pin "10") (pinfunction "1_10") (pintype "passive"))
      (node (ref "X5") (pin "2") (pinfunction "1_2") (pintype "passive"))
      (node (ref "X5") (pin "4") (pinfunction "1_4") (pintype "passive"))
      (node (ref "X5") (pin "6") (pinfunction "1_6") (pintype "passive"))
      (node (ref "X5") (pin "8") (pinfunction "1_8") (pintype "passive"))
      (node (ref "ZENER") (pin "A") (pinfunction "A_A") (pintype "passive"))
    )
    (net (code "5") (name "Net-(C1-Pad1)") (class "Default")
      (node (ref "C1") (pin "1") (pinfunction "1_1") (pintype "passive"))
      (node (ref "PUR1") (pin "2") (pinfunction "2_2") (pintype "passive"))
      (node (ref "SER1") (pin "1") (pinfunction "1_1") (pintype "passive"))
      (node (ref "X3") (pin "1") (pinfunction "1_1") (pintype "passive"))
    )
    (net (code "6") (name "Net-(C6SER-PadP$2)") (class "Default")
      (node (ref "C6SER") (pin "P$2") (pinfunction "P$2_P$2") (pintype "bidirectional"))
      (node (ref "SERSER") (pin "1") (pinfunction "1_1") (pintype "passive"))
      (node (ref "U$23") (pin "P$2") (pinfunction "P$2_P$2") (pintype "bidirectional"))
      (node (ref "U$24") (pin "P$1") (pinfunction "P$1_P$1") (pintype "bidirectional"))
    )
    (net (code "7") (name "Net-(FBD11-A)") (class "Default")
      (node (ref "FBD11") (pin "2") (pinfunction "A_2") (pintype "passive"))
      (node (ref "FUSE11") (pin "P$2") (pinfunction "P$2_P$2") (pintype "bidirectional"))
      (node (ref "LED11") (pin "-") (pinfunction "-_-") (pintype "passive"))
      (node (ref "OUTPUT1") (pin "2") (pinfunction "1_2") (pintype "passive"))
      (node (ref "POLYFUSE11") (pin "2") (pinfunction "P$2_2") (pintype "bidirectional"))
      (node (ref "PUOR11") (pin "1") (pinfunction "1_1") (pintype "passive"))
    )
    (net (code "8") (name "Net-(FBD11-C)") (class "Default")
      (node (ref "FBD11") (pin "1") (pinfunction "C_1") (pintype "passive"))
      (node (ref "FBD12") (pin "1") (pinfunction "C_1") (pintype "passive"))
      (node (ref "FBD13") (pin "1") (pinfunction "C_1") (pintype "passive"))
      (node (ref "FBD14") (pin "1") (pinfunction "C_1") (pintype "passive"))
      (node (ref "FBD15") (pin "1") (pinfunction "C_1") (pintype "passive"))
      (node (ref "FBD16") (pin "1") (pinfunction "C_1") (pintype "passive"))
      (node (ref "FBD17") (pin "1") (pinfunction "C_1") (pintype "passive"))
      (node (ref "FBD18") (pin "1") (pinfunction "C_1") (pintype "passive"))
      (node (ref "FBD19") (pin "1") (pinfunction "C_1") (pintype "passive"))
      (node (ref "FBD20") (pin "1") (pinfunction "C_1") (pintype "passive"))
      (node (ref "LEDR11") (pin "2") (pinfunction "2_2") (pintype "passive"))
      (node (ref "LEDR12") (pin "2") (pinfunction "2_2") (pintype "passive"))
      (node (ref "LEDR13") (pin "2") (pinfunction "2_2") (pintype "passive"))
      (node (ref "LEDR14") (pin "2") (pinfunction "2_2") (pintype "passive"))
      (node (ref "LEDR15") (pin "2") (pinfunction "2_2") (pintype "passive"))
      (node (ref "LEDR16") (pin "2") (pinfunction "2_2") (pintype "passive"))
      (node (ref "LEDR17") (pin "2") (pinfunction "2_2") (pintype "passive"))
      (node (ref "LEDR18") (pin "2") (pinfunction "2_2") (pintype "passive"))
      (node (ref "LEDR19") (pin "2") (pinfunction "2_2") (pintype "passive"))
      (node (ref "LEDR20") (pin "2") (pinfunction "2_2") (pintype "passive"))
      (node (ref "OUTPUT1") (pin "1") (pinfunction "1_1") (pintype "passive"))
      (node (ref "OUTPUT1") (pin "3") (pinfunction "1_3") (pintype "passive"))
      (node (ref "OUTPUT1") (pin "5") (pinfunction "1_5") (pintype "passive"))
      (node (ref "OUTPUT1") (pin "7") (pinfunction "1_7") (pintype "passive"))
      (node (ref "OUTPUT1") (pin "9") (pinfunction "1_9") (pintype "passive"))
      (node (ref "OUTPUT2") (pin "1") (pinfunction "1_1") (pintype "passive"))
      (node (ref "OUTPUT2") (pin "3") (pinfunction "1_3") (pintype "passive"))
      (node (ref "OUTPUT2") (pin "5") (pinfunction "1_5") (pintype "passive"))
      (node (ref "OUTPUT2") (pin "7") (pinfunction "1_7") (pintype "passive"))
      (node (ref "OUTPUT2") (pin "9") (pinfunction "1_9") (pintype "passive"))
      (node (ref "PUOR11") (pin "2") (pinfunction "2_2") (pintype "passive"))
      (node (ref "PUOR12") (pin "2") (pinfunction "2_2") (pintype "passive"))
      (node (ref "PUOR13") (pin "2") (pinfunction "2_2") (pintype "passive"))
      (node (ref "PUOR14") (pin "2") (pinfunction "2_2") (pintype "passive"))
      (node (ref "PUOR15") (pin "2") (pinfunction "2_2") (pintype "passive"))
      (node (ref "PUOR16") (pin "2") (pinfunction "2_2") (pintype "passive"))
      (node (ref "PUOR17") (pin "2") (pinfunction "2_2") (pintype "passive"))
      (node (ref "PUOR18") (pin "2") (pinfunction "2_2") (pintype "passive"))
      (node (ref "PUOR19") (pin "2") (pinfunction "2_2") (pintype "passive"))
      (node (ref "PUOR20") (pin "2") (pinfunction "2_2") (pintype "passive"))
      (node (ref "SOURCE") (pin "2") (pinfunction "2_2") (pintype "passive"))
    )
    (net (code "9") (name "Net-(FBD12-A)") (class "Default")
      (node (ref "FBD12") (pin "2") (pinfunction "A_2") (pintype "passive"))
      (node (ref "FUSE12") (pin "P$2") (pinfunction "P$2_P$2") (pintype "bidirectional"))
      (node (ref "LED12") (pin "-") (pinfunction "-_-") (pintype "passive"))
      (node (ref "OUTPUT1") (pin "4") (pinfunction "1_4") (pintype "passive"))
      (node (ref "POLYFUSE12") (pin "2") (pinfunction "P$2_2") (pintype "bidirectional"))
      (node (ref "PUOR12") (pin "1") (pinfunction "1_1") (pintype "passive"))
    )
    (net (code "10") (name "Net-(FBD13-A)") (class "Default")
      (node (ref "FBD13") (pin "2") (pinfunction "A_2") (pintype "passive"))
      (node (ref "FUSE13") (pin "P$2") (pinfunction "P$2_P$2") (pintype "bidirectional"))
      (node (ref "LED13") (pin "-") (pinfunction "-_-") (pintype "passive"))
      (node (ref "OUTPUT1") (pin "6") (pinfunction "1_6") (pintype "passive"))
      (node (ref "POLYFUSE13") (pin "2") (pinfunction "P$2_2") (pintype "bidirectional"))
      (node (ref "PUOR13") (pin "1") (pinfunction "1_1") (pintype "passive"))
    )
    (net (code "11") (name "Net-(FBD14-A)") (class "Default")
      (node (ref "FBD14") (pin "2") (pinfunction "A_2") (pintype "passive"))
      (node (ref "FUSE14") (pin "P$2") (pinfunction "P$2_P$2") (pintype "bidirectional"))
      (node (ref "LED14") (pin "-") (pinfunction "-_-") (pintype "passive"))
      (node (ref "OUTPUT1") (pin "8") (pinfunction "1_8") (pintype "passive"))
      (node (ref "POLYFUSE14") (pin "2") (pinfunction "P$2_2") (pintype "bidirectional"))
      (node (ref "PUOR14") (pin "1") (pinfunction "1_1") (pintype "passive"))
    )
    (net (code "12") (name "Net-(FBD15-A)") (class "Default")
      (node (ref "FBD15") (pin "2") (pinfunction "A_2") (pintype "passive"))
      (node (ref "FUSE15") (pin "P$2") (pinfunction "P$2_P$2") (pintype "bidirectional"))
      (node (ref "LED15") (pin "-") (pinfunction "-_-") (pintype "passive"))
      (node (ref "OUTPUT1") (pin "10") (pinfunction "1_10") (pintype "passive"))
      (node (ref "POLYFUSE15") (pin "2") (pinfunction "P$2_2") (pintype "bidirectional"))
      (node (ref "PUOR15") (pin "1") (pinfunction "1_1") (pintype "passive"))
    )
    (net (code "13") (name "Net-(FBD16-A)") (class "Default")
      (node (ref "FBD16") (pin "2") (pinfunction "A_2") (pintype "passive"))
      (node (ref "FUSE16") (pin "P$2") (pinfunction "P$2_P$2") (pintype "bidirectional"))
      (node (ref "LED16") (pin "-") (pinfunction "-_-") (pintype "passive"))
      (node (ref "OUTPUT2") (pin "2") (pinfunction "1_2") (pintype "passive"))
      (node (ref "POLYFUSE16") (pin "2") (pinfunction "P$2_2") (pintype "bidirectional"))
      (node (ref "PUOR16") (pin "1") (pinfunction "1_1") (pintype "passive"))
    )
    (net (code "14") (name "Net-(FBD17-A)") (class "Default")
      (node (ref "FBD17") (pin "2") (pinfunction "A_2") (pintype "passive"))
      (node (ref "FUSE17") (pin "P$2") (pinfunction "P$2_P$2") (pintype "bidirectional"))
      (node (ref "LED17") (pin "-") (pinfunction "-_-") (pintype "passive"))
      (node (ref "OUTPUT2") (pin "4") (pinfunction "1_4") (pintype "passive"))
      (node (ref "POLYFUSE17") (pin "2") (pinfunction "P$2_2") (pintype "bidirectional"))
      (node (ref "PUOR17") (pin "1") (pinfunction "1_1") (pintype "passive"))
    )
    (net (code "15") (name "Net-(FBD18-A)") (class "Default")
      (node (ref "FBD18") (pin "2") (pinfunction "A_2") (pintype "passive"))
      (node (ref "FUSE18") (pin "P$2") (pinfunction "P$2_P$2") (pintype "bidirectional"))
      (node (ref "LED18") (pin "-") (pinfunction "-_-") (pintype "passive"))
      (node (ref "OUTPUT2") (pin "6") (pinfunction "1_6") (pintype "passive"))
      (node (ref "POLYFUSE18") (pin "2") (pinfunction "P$2_2") (pintype "bidirectional"))
      (node (ref "PUOR18") (pin "1") (pinfunction "1_1") (pintype "passive"))
    )
    (net (code "16") (name "Net-(FBD19-A)") (class "Default")
      (node (ref "FBD19") (pin "2") (pinfunction "A_2") (pintype "passive"))
      (node (ref "FUSE9") (pin "P$2") (pinfunction "P$2_P$2") (pintype "bidirectional"))
      (node (ref "LED19") (pin "-") (pinfunction "-_-") (pintype "passive"))
      (node (ref "OUTPUT2") (pin "8") (pinfunction "1_8") (pintype "passive"))
      (node (ref "POLYFUSE19") (pin "2") (pinfunction "P$2_2") (pintype "bidirectional"))
      (node (ref "PUOR19") (pin "1") (pinfunction "1_1") (pintype "passive"))
    )
    (net (code "17") (name "Net-(FBD20-A)") (class "Default")
      (node (ref "FBD20") (pin "2") (pinfunction "A_2") (pintype "passive"))
      (node (ref "FUSE20") (pin "P$2") (pinfunction "P$2_P$2") (pintype "bidirectional"))
      (node (ref "LED20") (pin "-") (pinfunction "-_-") (pintype "passive"))
      (node (ref "OUTPUT2") (pin "10") (pinfunction "1_10") (pintype "passive"))
      (node (ref "POLYFUSE20") (pin "2") (pinfunction "P$2_2") (pintype "bidirectional"))
      (node (ref "PUOR20") (pin "1") (pinfunction "1_1") (pintype "passive"))
    )
    (net (code "18") (name "Net-(IC1-INT{slash}RB0)") (class "Default")
      (node (ref "IC1") (pin "21") (pinfunction "INT/RB0_21") (pintype "bidirectional"))
      (node (ref "SER2") (pin "2") (pinfunction "2_2") (pintype "passive"))
    )
    (net (code "19") (name "Net-(IC1-MCLR#{slash}THV)") (class "Default")
      (node (ref "IC1") (pin "1") (pinfunction "MCLR#/THV_1") (pintype "input"))
      (node (ref "ISCPRES") (pin "1") (pinfunction "1_1") (pintype "passive"))
      (node (ref "OPTION") (pin "1") (pinfunction "1_1") (pintype "passive"))
      (node (ref "RESET") (pin "2") (pinfunction "2_2") (pintype "passive"))
    )
    (net (code "20") (name "Net-(IC1-OSC1{slash}CLKIN)") (class "Default")
      (node (ref "IC1") (pin "9") (pinfunction "OSC1/CLKIN_9") (pintype "input"))
      (node (ref "Q21") (pin "1") (pinfunction "1_1") (pintype "passive"))
    )
    (net (code "21") (name "Net-(IC1-OSC2{slash}CLKOUT)") (class "Default")
      (node (ref "IC1") (pin "10") (pinfunction "OSC2/CLKOUT_10") (pintype "output"))
      (node (ref "Q21") (pin "2") (pinfunction "2_2") (pintype "passive"))
    )
    (net (code "22") (name "Net-(IC1-PGC{slash}RB6)") (class "Default")
      (node (ref "IC1") (pin "27") (pinfunction "PGC/RB6_27") (pintype "bidirectional"))
      (node (ref "ICSP") (pin "5") (pinfunction "5_5") (pintype "passive"))
    )
    (net (code "23") (name "Net-(IC1-PGD{slash}RB7)") (class "Default")
      (node (ref "IC1") (pin "28") (pinfunction "PGD/RB7_28") (pintype "bidirectional"))
      (node (ref "ICSP") (pin "4") (pinfunction "4_4") (pintype "passive"))
    )
    (net (code "24") (name "Net-(IC1-PGM{slash}RB3)") (class "Default")
      (node (ref "IC1") (pin "24") (pinfunction "PGM/RB3_24") (pintype "bidirectional"))
      (node (ref "SER7") (pin "2") (pinfunction "2_2") (pintype "passive"))
    )
    (net (code "25") (name "Net-(IC1-RA0{slash}AN0)") (class "Default")
      (node (ref "IC1") (pin "2") (pinfunction "RA0/AN0_2") (pintype "bidirectional"))
      (node (ref "SER8") (pin "1") (pinfunction "1_1") (pintype "passive"))
    )
    (net (code "26") (name "Net-(IC1-RA1{slash}AN1)") (class "Default")
      (node (ref "IC1") (pin "3") (pinfunction "RA1/AN1_3") (pintype "bidirectional"))
      (node (ref "IN/OUT/OW") (pin "2") (pinfunction "2_2") (pintype "passive"))
      (node (ref "SER18") (pin "1") (pinfunction "1_1") (pintype "passive"))
      (node (ref "U$1") (pin "9") (pinfunction "P$9_9") (pintype "bidirectional"))
    )
    (net (code "27") (name "Net-(IC1-RA2{slash}AN2)") (class "Default")
      (node (ref "IC1") (pin "4") (pinfunction "RA2/AN2_4") (pintype "bidirectional"))
      (node (ref "SER5") (pin "2") (pinfunction "2_2") (pintype "passive"))
      (node (ref "U$1") (pin "10") (pinfunction "P$10_10") (pintype "bidirectional"))
    )
    (net (code "28") (name "Net-(IC1-RA3{slash}AN3)") (class "Default")
      (node (ref "IC1") (pin "5") (pinfunction "RA3/AN3_5") (pintype "bidirectional"))
      (node (ref "SER4") (pin "2") (pinfunction "2_2") (pintype "passive"))
      (node (ref "U$2") (pin "6") (pinfunction "P$6_6") (pintype "bidirectional"))
    )
    (net (code "29") (name "Net-(IC1-RA4{slash}T0CKI)") (class "Default")
      (node (ref "IC1") (pin "6") (pinfunction "RA4/T0CKI_6") (pintype "bidirectional"))
      (node (ref "SER3") (pin "2") (pinfunction "2_2") (pintype "passive"))
    )
    (net (code "30") (name "Net-(IC1-RA5{slash}AN4)") (class "Default")
      (node (ref "IC1") (pin "7") (pinfunction "RA5/AN4_7") (pintype "bidirectional"))
      (node (ref "SER17") (pin "1") (pinfunction "1_1") (pintype "passive"))
    )
    (net (code "31") (name "Net-(IC1-RB1)") (class "Default")
      (node (ref "IC1") (pin "22") (pinfunction "RB1_22") (pintype "bidirectional"))
      (node (ref "SER6") (pin "2") (pinfunction "2_2") (pintype "passive"))
    )
    (net (code "32") (name "Net-(IC1-RB2)") (class "Default")
      (node (ref "IC1") (pin "23") (pinfunction "RB2_23") (pintype "bidirectional"))
      (node (ref "SER1") (pin "2") (pinfunction "2_2") (pintype "passive"))
    )
    (net (code "33") (name "Net-(IC1-RB4)") (class "Default")
      (node (ref "IC1") (pin "25") (pinfunction "RB4_25") (pintype "bidirectional"))
      (node (ref "SER16") (pin "1") (pinfunction "1_1") (pintype "passive"))
      (node (ref "U$24") (pin "P$2") (pinfunction "P$2_P$2") (pintype "bidirectional"))
    )
    (net (code "34") (name "Net-(IC1-RB5)") (class "Default")
      (node (ref "IC1") (pin "26") (pinfunction "RB5_26") (pintype "bidirectional"))
      (node (ref "SER15") (pin "1") (pinfunction "1_1") (pintype "passive"))
    )
    (net (code "35") (name "Net-(IC1-RC0{slash}T1OSO)") (class "Default")
      (node (ref "IC1") (pin "11") (pinfunction "RC0/T1OSO_11") (pintype "bidirectional"))
      (node (ref "SER14") (pin "1") (pinfunction "1_1") (pintype "passive"))
    )
    (net (code "36") (name "Net-(IC1-RC1{slash}T1OSI)") (class "Default")
      (node (ref "IC1") (pin "12") (pinfunction "RC1/T1OSI_12") (pintype "bidirectional"))
      (node (ref "SER13") (pin "1") (pinfunction "1_1") (pintype "passive"))
    )
    (net (code "37") (name "Net-(IC1-RC2{slash}CCP1)") (class "Default")
      (node (ref "IC1") (pin "13") (pinfunction "RC2/CCP1_13") (pintype "bidirectional"))
      (node (ref "SER12") (pin "1") (pinfunction "1_1") (pintype "passive"))
    )
    (net (code "38") (name "Net-(IC1-RC3{slash}SCK)") (class "Default")
      (node (ref "IC1") (pin "14") (pinfunction "RC3/SCK_14") (pintype "bidirectional"))
      (node (ref "SER11") (pin "1") (pinfunction "1_1") (pintype "passive"))
      (node (ref "U$2") (pin "5") (pinfunction "P$5_5") (pintype "bidirectional"))
    )
    (net (code "39") (name "Net-(IC1-RC6)") (class "Default")
      (node (ref "IC1") (pin "17") (pinfunction "RC6_17") (pintype "bidirectional"))
      (node (ref "SER9") (pin "2") (pinfunction "2_2") (pintype "passive"))
    )
    (net (code "40") (name "Net-(IC1-RC7)") (class "Default")
      (node (ref "IC1") (pin "18") (pinfunction "RC7_18") (pintype "bidirectional"))
      (node (ref "SER10") (pin "2") (pinfunction "2_2") (pintype "passive"))
    )
    (net (code "41") (name "Net-(IC1-SDI{slash}RC4)") (class "Default")
      (node (ref "IC1") (pin "15") (pinfunction "SDI/RC4_15") (pintype "bidirectional"))
      (node (ref "SER20") (pin "1") (pinfunction "1_1") (pintype "passive"))
      (node (ref "U$2") (pin "7") (pinfunction "P$7_7") (pintype "bidirectional"))
    )
    (net (code "42") (name "Net-(IC1-SDO{slash}RC5)") (class "Default")
      (node (ref "IC1") (pin "16") (pinfunction "SDO/RC5_16") (pintype "bidirectional"))
      (node (ref "SER19") (pin "1") (pinfunction "1_1") (pintype "passive"))
    )
    (net (code "43") (name "Net-(ICSP-Pad1)") (class "Default")
      (node (ref "ICSP") (pin "1") (pinfunction "1_1") (pintype "passive"))
      (node (ref "OPTION") (pin "2") (pinfunction "2_2") (pintype "passive"))
    )
    (net (code "44") (name "Net-(LED11-Pad+)") (class "Default")
      (node (ref "LED11") (pin "+") (pinfunction "+_+") (pintype "passive"))
      (node (ref "LEDR11") (pin "1") (pinfunction "1_1") (pintype "passive"))
    )
    (net (code "45") (name "Net-(LED12-Pad+)") (class "Default")
      (node (ref "LED12") (pin "+") (pinfunction "+_+") (pintype "passive"))
      (node (ref "LEDR12") (pin "1") (pinfunction "1_1") (pintype "passive"))
    )
    (net (code "46") (name "Net-(LED13-Pad+)") (class "Default")
      (node (ref "LED13") (pin "+") (pinfunction "+_+") (pintype "passive"))
      (node (ref "LEDR13") (pin "1") (pinfunction "1_1") (pintype "passive"))
    )
    (net (code "47") (name "Net-(LED14-Pad+)") (class "Default")
      (node (ref "LED14") (pin "+") (pinfunction "+_+") (pintype "passive"))
      (node (ref "LEDR14") (pin "1") (pinfunction "1_1") (pintype "passive"))
    )
    (net (code "48") (name "Net-(LED15-Pad+)") (class "Default")
      (node (ref "LED15") (pin "+") (pinfunction "+_+") (pintype "passive"))
      (node (ref "LEDR15") (pin "1") (pinfunction "1_1") (pintype "passive"))
    )
    (net (code "49") (name "Net-(LED16-Pad+)") (class "Default")
      (node (ref "LED16") (pin "+") (pinfunction "+_+") (pintype "passive"))
      (node (ref "LEDR16") (pin "1") (pinfunction "1_1") (pintype "passive"))
    )
    (net (code "50") (name "Net-(LED17-Pad+)") (class "Default")
      (node (ref "LED17") (pin "+") (pinfunction "+_+") (pintype "passive"))
      (node (ref "LEDR17") (pin "1") (pinfunction "1_1") (pintype "passive"))
    )
    (net (code "51") (name "Net-(LED18-Pad+)") (class "Default")
      (node (ref "LED18") (pin "+") (pinfunction "+_+") (pintype "passive"))
      (node (ref "LEDR18") (pin "1") (pinfunction "1_1") (pintype "passive"))
    )
    (net (code "52") (name "Net-(LED19-Pad+)") (class "Default")
      (node (ref "LED19") (pin "+") (pinfunction "+_+") (pintype "passive"))
      (node (ref "LEDR19") (pin "1") (pinfunction "1_1") (pintype "passive"))
    )
    (net (code "53") (name "Net-(LED20-Pad+)") (class "Default")
      (node (ref "LED20") (pin "+") (pinfunction "+_+") (pintype "passive"))
      (node (ref "LEDR20") (pin "1") (pinfunction "1_1") (pintype "passive"))
    )
    (net (code "54") (name "Net-(LED100-Pad-)") (class "Default")
      (node (ref "LED100") (pin "-") (pinfunction "-_-") (pintype "passive"))
      (node (ref "LEDRESEXTRA") (pin "1") (pinfunction "1_1") (pintype "passive"))
    )
    (net (code "55") (name "Net-(LED200-Pad-)") (class "Default")
      (node (ref "LED200") (pin "-") (pinfunction "-_-") (pintype "passive"))
      (node (ref "LEDRESMAIN") (pin "1") (pinfunction "1_1") (pintype "passive"))
    )
    (net (code "56") (name "Net-(POLYFUSE11-P$1)") (class "Default")
      (node (ref "FUSE11") (pin "P$1") (pinfunction "P$1_P$1") (pintype "bidirectional"))
      (node (ref "POLYFUSE11") (pin "1") (pinfunction "P$1_1") (pintype "bidirectional"))
      (node (ref "TR-A11") (pin "2") (pinfunction "D_2") (pintype "passive"))
      (node (ref "TR-B11") (pin "D") (pinfunction "D_D") (pintype "passive"))
    )
    (net (code "57") (name "Net-(POLYFUSE12-P$1)") (class "Default")
      (node (ref "FUSE12") (pin "P$1") (pinfunction "P$1_P$1") (pintype "bidirectional"))
      (node (ref "POLYFUSE12") (pin "1") (pinfunction "P$1_1") (pintype "bidirectional"))
      (node (ref "TR-A12") (pin "2") (pinfunction "D_2") (pintype "passive"))
      (node (ref "TR-B12") (pin "D") (pinfunction "D_D") (pintype "passive"))
    )
    (net (code "58") (name "Net-(POLYFUSE13-P$1)") (class "Default")
      (node (ref "FUSE13") (pin "P$1") (pinfunction "P$1_P$1") (pintype "bidirectional"))
      (node (ref "POLYFUSE13") (pin "1") (pinfunction "P$1_1") (pintype "bidirectional"))
      (node (ref "TR-A13") (pin "2") (pinfunction "D_2") (pintype "passive"))
      (node (ref "TR-B13") (pin "D") (pinfunction "D_D") (pintype "passive"))
    )
    (net (code "59") (name "Net-(POLYFUSE14-P$1)") (class "Default")
      (node (ref "FUSE14") (pin "P$1") (pinfunction "P$1_P$1") (pintype "bidirectional"))
      (node (ref "POLYFUSE14") (pin "1") (pinfunction "P$1_1") (pintype "bidirectional"))
      (node (ref "TR-A14") (pin "2") (pinfunction "D_2") (pintype "passive"))
      (node (ref "TR-B14") (pin "D") (pinfunction "D_D") (pintype "passive"))
    )
    (net (code "60") (name "Net-(POLYFUSE15-P$1)") (class "Default")
      (node (ref "FUSE15") (pin "P$1") (pinfunction "P$1_P$1") (pintype "bidirectional"))
      (node (ref "POLYFUSE15") (pin "1") (pinfunction "P$1_1") (pintype "bidirectional"))
      (node (ref "TR-A15") (pin "2") (pinfunction "D_2") (pintype "passive"))
      (node (ref "TR-B15") (pin "D") (pinfunction "D_D") (pintype "passive"))
    )
    (net (code "61") (name "Net-(POLYFUSE16-P$1)") (class "Default")
      (node (ref "FUSE16") (pin "P$1") (pinfunction "P$1_P$1") (pintype "bidirectional"))
      (node (ref "POLYFUSE16") (pin "1") (pinfunction "P$1_1") (pintype "bidirectional"))
      (node (ref "TR-A16") (pin "2") (pinfunction "D_2") (pintype "passive"))
      (node (ref "TR-B16") (pin "D") (pinfunction "D_D") (pintype "passive"))
    )
    (net (code "62") (name "Net-(POLYFUSE17-P$1)") (class "Default")
      (node (ref "FUSE17") (pin "P$1") (pinfunction "P$1_P$1") (pintype "bidirectional"))
      (node (ref "POLYFUSE17") (pin "1") (pinfunction "P$1_1") (pintype "bidirectional"))
      (node (ref "TR-A17") (pin "2") (pinfunction "D_2") (pintype "passive"))
      (node (ref "TR-B17") (pin "D") (pinfunction "D_D") (pintype "passive"))
    )
    (net (code "63") (name "Net-(POLYFUSE18-P$1)") (class "Default")
      (node (ref "FUSE18") (pin "P$1") (pinfunction "P$1_P$1") (pintype "bidirectional"))
      (node (ref "POLYFUSE18") (pin "1") (pinfunction "P$1_1") (pintype "bidirectional"))
      (node (ref "TR-A18") (pin "2") (pinfunction "D_2") (pintype "passive"))
      (node (ref "TR-B18") (pin "D") (pinfunction "D_D") (pintype "passive"))
    )
    (net (code "64") (name "Net-(POLYFUSE19-P$1)") (class "Default")
      (node (ref "FUSE9") (pin "P$1") (pinfunction "P$1_P$1") (pintype "bidirectional"))
      (node (ref "POLYFUSE19") (pin "1") (pinfunction "P$1_1") (pintype "bidirectional"))
      (node (ref "TR-A19") (pin "2") (pinfunction "D_2") (pintype "passive"))
      (node (ref "TR-B19") (pin "D") (pinfunction "D_D") (pintype "passive"))
    )
    (net (code "65") (name "Net-(POLYFUSE20-P$1)") (class "Default")
      (node (ref "FUSE20") (pin "P$1") (pinfunction "P$1_P$1") (pintype "bidirectional"))
      (node (ref "POLYFUSE20") (pin "1") (pinfunction "P$1_1") (pintype "bidirectional"))
      (node (ref "TR-A20") (pin "2") (pinfunction "D_2") (pintype "passive"))
      (node (ref "TR-B20") (pin "D") (pinfunction "D_D") (pintype "passive"))
    )
    (net (code "66") (name "Net-(POLYFUSE100-P$2)") (class "Default")
      (node (ref "CEXTRA") (pin "1") (pinfunction "1_1") (pintype "passive"))
      (node (ref "POLYFUSE100") (pin "2") (pinfunction "P$2_2") (pintype "bidirectional"))
      (node (ref "VR3") (pin "1") (pinfunction "VI_1") (pintype "input"))
      (node (ref "VR4") (pin "1") (pinfunction "VI_1") (pintype "input"))
    )
    (net (code "67") (name "Net-(POLYFUSE200-P$2)") (class "Default")
      (node (ref "CMAIN") (pin "1") (pinfunction "1_1") (pintype "passive"))
      (node (ref "POLYFUSE200") (pin "2") (pinfunction "P$2_2") (pintype "bidirectional"))
      (node (ref "VR1") (pin "1") (pinfunction "VI_1") (pintype "input"))
      (node (ref "VR2") (pin "1") (pinfunction "VI_1") (pintype "input"))
    )
    (net (code "68") (name "Net-(TCB-1)") (class "Default")
      (node (ref "TC") (pin "2") (pinfunction "1_2") (pintype "passive"))
      (node (ref "U$2") (pin "3") (pinfunction "P$3_3") (pintype "bidirectional"))
    )
    (net (code "69") (name "Net-(TR-A11-G)") (class "Default")
      (node (ref "PDR11") (pin "1") (pinfunction "1_1") (pintype "passive"))
      (node (ref "PUR11/SCK") (pin "2") (pinfunction "2_2") (pintype "passive"))
      (node (ref "SER11") (pin "2") (pinfunction "2_2") (pintype "passive"))
      (node (ref "TR-A11") (pin "1") (pinfunction "G_1") (pintype "passive"))
      (node (ref "TR-B11") (pin "G") (pinfunction "G_G") (pintype "passive"))
      (node (ref "X4") (pin "1") (pinfunction "1_1") (pintype "passive"))
    )
    (net (code "70") (name "Net-(TR-A12-G)") (class "Default")
      (node (ref "PDR12") (pin "1") (pinfunction "1_1") (pintype "passive"))
      (node (ref "PUR12") (pin "2") (pinfunction "2_2") (pintype "passive"))
      (node (ref "SER12") (pin "2") (pinfunction "2_2") (pintype "passive"))
      (node (ref "TR-A12") (pin "1") (pinfunction "G_1") (pintype "passive"))
      (node (ref "TR-B12") (pin "G") (pinfunction "G_G") (pintype "passive"))
      (node (ref "X4") (pin "2") (pinfunction "1_2") (pintype "passive"))
    )
    (net (code "71") (name "Net-(TR-A13-G)") (class "Default")
      (node (ref "PDR13") (pin "1") (pinfunction "1_1") (pintype "passive"))
      (node (ref "PUR13") (pin "2") (pinfunction "2_2") (pintype "passive"))
      (node (ref "SER13") (pin "2") (pinfunction "2_2") (pintype "passive"))
      (node (ref "TR-A13") (pin "1") (pinfunction "G_1") (pintype "passive"))
      (node (ref "TR-B13") (pin "G") (pinfunction "G_G") (pintype "passive"))
      (node (ref "X4") (pin "3") (pinfunction "1_3") (pintype "passive"))
    )
    (net (code "72") (name "Net-(TR-A14-G)") (class "Default")
      (node (ref "PDR14") (pin "1") (pinfunction "1_1") (pintype "passive"))
      (node (ref "PUR14") (pin "2") (pinfunction "2_2") (pintype "passive"))
      (node (ref "SER14") (pin "2") (pinfunction "2_2") (pintype "passive"))
      (node (ref "TR-A14") (pin "1") (pinfunction "G_1") (pintype "passive"))
      (node (ref "TR-B14") (pin "G") (pinfunction "G_G") (pintype "passive"))
      (node (ref "X4") (pin "4") (pinfunction "1_4") (pintype "passive"))
    )
    (net (code "73") (name "Net-(TR-A15-G)") (class "Default")
      (node (ref "PDR15") (pin "1") (pinfunction "1_1") (pintype "passive"))
      (node (ref "PUR15") (pin "1") (pinfunction "1_1") (pintype "passive"))
      (node (ref "SER15") (pin "2") (pinfunction "2_2") (pintype "passive"))
      (node (ref "TR-A15") (pin "1") (pinfunction "G_1") (pintype "passive"))
      (node (ref "TR-B15") (pin "G") (pinfunction "G_G") (pintype "passive"))
      (node (ref "X4") (pin "5") (pinfunction "1_5") (pintype "passive"))
    )
    (net (code "74") (name "Net-(TR-A16-G)") (class "Default")
      (node (ref "PDR16") (pin "1") (pinfunction "1_1") (pintype "passive"))
      (node (ref "PUR16") (pin "1") (pinfunction "1_1") (pintype "passive"))
      (node (ref "SER16") (pin "2") (pinfunction "2_2") (pintype "passive"))
      (node (ref "TR-A16") (pin "1") (pinfunction "G_1") (pintype "passive"))
      (node (ref "TR-B16") (pin "G") (pinfunction "G_G") (pintype "passive"))
      (node (ref "X4") (pin "6") (pinfunction "1_6") (pintype "passive"))
    )
    (net (code "75") (name "Net-(TR-A17-G)") (class "Default")
      (node (ref "PDR17") (pin "1") (pinfunction "1_1") (pintype "passive"))
      (node (ref "PUR17") (pin "1") (pinfunction "1_1") (pintype "passive"))
      (node (ref "SER17") (pin "2") (pinfunction "2_2") (pintype "passive"))
      (node (ref "TR-A17") (pin "1") (pinfunction "G_1") (pintype "passive"))
      (node (ref "TR-B17") (pin "G") (pinfunction "G_G") (pintype "passive"))
      (node (ref "X4") (pin "7") (pinfunction "1_7") (pintype "passive"))
    )
    (net (code "76") (name "Net-(TR-A18-G)") (class "Default")
      (node (ref "PDR18") (pin "1") (pinfunction "1_1") (pintype "passive"))
      (node (ref "PUR18") (pin "1") (pinfunction "1_1") (pintype "passive"))
      (node (ref "SER18") (pin "2") (pinfunction "2_2") (pintype "passive"))
      (node (ref "TR-A18") (pin "1") (pinfunction "G_1") (pintype "passive"))
      (node (ref "TR-B18") (pin "G") (pinfunction "G_G") (pintype "passive"))
      (node (ref "X4") (pin "8") (pinfunction "1_8") (pintype "passive"))
    )
    (net (code "77") (name "Net-(TR-A19-G)") (class "Default")
      (node (ref "PDR19") (pin "1") (pinfunction "1_1") (pintype "passive"))
      (node (ref "PUR19/SDO") (pin "1") (pinfunction "1_1") (pintype "passive"))
      (node (ref "SER19") (pin "2") (pinfunction "2_2") (pintype "passive"))
      (node (ref "TR-A19") (pin "1") (pinfunction "G_1") (pintype "passive"))
      (node (ref "TR-B19") (pin "G") (pinfunction "G_G") (pintype "passive"))
      (node (ref "X4") (pin "9") (pinfunction "1_9") (pintype "passive"))
    )
    (net (code "78") (name "Net-(TR-A20-G)") (class "Default")
      (node (ref "PDR20") (pin "1") (pinfunction "1_1") (pintype "passive"))
      (node (ref "PUR20/SDI") (pin "1") (pinfunction "1_1") (pintype "passive"))
      (node (ref "SER20") (pin "2") (pinfunction "2_2") (pintype "passive"))
      (node (ref "TR-A20") (pin "1") (pinfunction "G_1") (pintype "passive"))
      (node (ref "TR-B20") (pin "G") (pinfunction "G_G") (pintype "passive"))
      (node (ref "X4") (pin "10") (pinfunction "1_10") (pintype "passive"))
    )
    (net (code "79") (name "Net-(TR-A111-D)") (class "Default")
      (node (ref "SERIAL") (pin "2") (pinfunction "2_2") (pintype "passive"))
      (node (ref "SERPUR") (pin "2") (pinfunction "2_2") (pintype "passive"))
      (node (ref "TR-A111") (pin "2") (pinfunction "D_2") (pintype "passive"))
      (node (ref "U$23") (pin "P$1") (pinfunction "P$1_P$1") (pintype "bidirectional"))
    )
    (net (code "80") (name "Net-(TR-A111-G)") (class "Default")
      (node (ref "SERPDR") (pin "1") (pinfunction "1_1") (pintype "passive"))
      (node (ref "SERSER") (pin "2") (pinfunction "2_2") (pintype "passive"))
      (node (ref "TR-A111") (pin "1") (pinfunction "G_1") (pintype "passive"))
    )
    (net (code "81") (name "Net-(U$1-P$1)") (class "Default")
      (node (ref "RC1") (pin "1") (pinfunction "1_1") (pintype "passive"))
      (node (ref "U$1") (pin "1") (pinfunction "P$1_1") (pintype "bidirectional"))
    )
    (net (code "82") (name "Net-(U$1-P$2)") (class "Default")
      (node (ref "RC4") (pin "1") (pinfunction "1_1") (pintype "passive"))
      (node (ref "RS232PWR") (pin "3") (pinfunction "3_3") (pintype "passive"))
      (node (ref "U$1") (pin "2") (pinfunction "P$2_2") (pintype "bidirectional"))
    )
    (net (code "83") (name "Net-(U$1-P$3)") (class "Default")
      (node (ref "RC1") (pin "2") (pinfunction "2_2") (pintype "passive"))
      (node (ref "U$1") (pin "3") (pinfunction "P$3_3") (pintype "bidirectional"))
    )
    (net (code "84") (name "Net-(U$1-P$4)") (class "Default")
      (node (ref "RC2") (pin "1") (pinfunction "1_1") (pintype "passive"))
      (node (ref "U$1") (pin "4") (pinfunction "P$4_4") (pintype "bidirectional"))
    )
    (net (code "85") (name "Net-(U$1-P$5)") (class "Default")
      (node (ref "RC2") (pin "2") (pinfunction "2_2") (pintype "passive"))
      (node (ref "U$1") (pin "5") (pinfunction "P$5_5") (pintype "bidirectional"))
    )
    (net (code "86") (name "Net-(U$1-P$6)") (class "Default")
      (node (ref "RC5") (pin "2") (pinfunction "2_2") (pintype "passive"))
      (node (ref "RS232PWR") (pin "2") (pinfunction "2_2") (pintype "passive"))
      (node (ref "U$1") (pin "6") (pinfunction "P$6_6") (pintype "bidirectional"))
    )
    (net (code "87") (name "Net-(U$1-P$7)") (class "Default")
      (node (ref "JP1") (pin "4") (pinfunction "4_4") (pintype "passive"))
      (node (ref "U$1") (pin "7") (pinfunction "P$7_7") (pintype "bidirectional"))
    )
    (net (code "88") (name "Net-(U$1-P$8)") (class "Default")
      (node (ref "JP1") (pin "3") (pinfunction "3_3") (pintype "passive"))
      (node (ref "U$1") (pin "8") (pinfunction "P$8_8") (pintype "bidirectional"))
    )
    (net (code "89") (name "Net-(U$1-P$11)") (class "Default")
      (node (ref "C6SER") (pin "P$1") (pinfunction "P$1_P$1") (pintype "bidirectional"))
      (node (ref "C9") (pin "1") (pinfunction "1_1") (pintype "passive"))
      (node (ref "PUR9") (pin "2") (pinfunction "2_2") (pintype "passive"))
      (node (ref "SER9") (pin "1") (pinfunction "1_1") (pintype "passive"))
      (node (ref "U$1") (pin "11") (pinfunction "P$11_11") (pintype "bidirectional"))
      (node (ref "X3") (pin "9") (pinfunction "1_9") (pintype "passive"))
    )
    (net (code "90") (name "Net-(U$1-P$12)") (class "Default")
      (node (ref "C10") (pin "1") (pinfunction "1_1") (pintype "passive"))
      (node (ref "PUR10") (pin "2") (pinfunction "2_2") (pintype "passive"))
      (node (ref "SER10") (pin "1") (pinfunction "1_1") (pintype "passive"))
      (node (ref "U$1") (pin "12") (pinfunction "P$12_12") (pintype "bidirectional"))
      (node (ref "X3") (pin "10") (pinfunction "1_10") (pintype "passive"))
    )
    (net (code "91") (name "Net-(U$1-P$13)") (class "Default")
      (node (ref "JP1") (pin "1") (pinfunction "1_1") (pintype "passive"))
      (node (ref "U$1") (pin "13") (pinfunction "P$13_13") (pintype "bidirectional"))
    )
    (net (code "92") (name "Net-(U$1-P$14)") (class "Default")
      (node (ref "JP1") (pin "2") (pinfunction "2_2") (pintype "passive"))
      (node (ref "U$1") (pin "14") (pinfunction "P$14_14") (pintype "bidirectional"))
    )
    (net (code "93") (name "Net-(U$4-OSCI)") (class "Default")
      (node (ref "Q22") (pin "2") (pinfunction "2_2") (pintype "passive"))
      (node (ref "U$4") (pin "1") (pinfunction "OSCI_1") (pintype "bidirectional"))
    )
    (net (code "94") (name "Net-(U$4-OSCO)") (class "Default")
      (node (ref "Q22") (pin "1") (pinfunction "1_1") (pintype "passive"))
      (node (ref "U$4") (pin "2") (pinfunction "OSCO_2") (pintype "bidirectional"))
    )
    (net (code "95") (name "Net-(U$4-VBAT)") (class "Default")
      (node (ref "BAT1") (pin "P$1") (pinfunction "P$1_P$1") (pintype "bidirectional"))
      (node (ref "U$4") (pin "3") (pinfunction "VBAT_3") (pintype "bidirectional"))
    )
    (net (code "96") (name "Net-(U$18-SCL)") (class "Default")
      (node (ref "C6") (pin "1") (pinfunction "1_1") (pintype "passive"))
      (node (ref "PUR6") (pin "2") (pinfunction "2_2") (pintype "passive"))
      (node (ref "SER6") (pin "1") (pinfunction "1_1") (pintype "passive"))
      (node (ref "U$18") (pin "6") (pinfunction "SCL_6") (pintype "bidirectional"))
      (node (ref "U$4") (pin "6") (pinfunction "SCL_6") (pintype "bidirectional"))
      (node (ref "X3") (pin "6") (pinfunction "1_6") (pintype "passive"))
    )
    (net (code "97") (name "Net-(U$18-SDA)") (class "Default")
      (node (ref "C7") (pin "1") (pinfunction "1_1") (pintype "passive"))
      (node (ref "PUR7") (pin "2") (pinfunction "2_2") (pintype "passive"))
      (node (ref "SER7") (pin "1") (pinfunction "1_1") (pintype "passive"))
      (node (ref "U$18") (pin "5") (pinfunction "SDA_5") (pintype "bidirectional"))
      (node (ref "U$4") (pin "5") (pinfunction "SDA_5") (pintype "bidirectional"))
      (node (ref "X3") (pin "7") (pinfunction "1_7") (pintype "passive"))
    )
    (net (code "98") (name "Net-(X3C-1)") (class "Default")
      (node (ref "C2") (pin "1") (pinfunction "1_1") (pintype "passive"))
      (node (ref "PUR2") (pin "2") (pinfunction "2_2") (pintype "passive"))
      (node (ref "SER2") (pin "1") (pinfunction "1_1") (pintype "passive"))
      (node (ref "X3") (pin "2") (pinfunction "1_2") (pintype "passive"))
    )
    (net (code "99") (name "Net-(X3D-1)") (class "Default")
      (node (ref "C3") (pin "1") (pinfunction "1_1") (pintype "passive"))
      (node (ref "PUR3") (pin "2") (pinfunction "2_2") (pintype "passive"))
      (node (ref "SER3") (pin "1") (pinfunction "1_1") (pintype "passive"))
      (node (ref "X3") (pin "3") (pinfunction "1_3") (pintype "passive"))
    )
    (net (code "100") (name "Net-(X3E-1)") (class "Default")
      (node (ref "C4") (pin "1") (pinfunction "1_1") (pintype "passive"))
      (node (ref "PUR4") (pin "2") (pinfunction "2_2") (pintype "passive"))
      (node (ref "SER4") (pin "1") (pinfunction "1_1") (pintype "passive"))
      (node (ref "X3") (pin "4") (pinfunction "1_4") (pintype "passive"))
    )
    (net (code "101") (name "Net-(X3F-1)") (class "Default")
      (node (ref "C5") (pin "1") (pinfunction "1_1") (pintype "passive"))
      (node (ref "PUR5") (pin "2") (pinfunction "2_2") (pintype "passive"))
      (node (ref "SER5") (pin "1") (pinfunction "1_1") (pintype "passive"))
      (node (ref "X3") (pin "5") (pinfunction "1_5") (pintype "passive"))
    )
    (net (code "102") (name "Net-(X3I-1)") (class "Default")
      (node (ref "C8") (pin "1") (pinfunction "1_1") (pintype "passive"))
      (node (ref "PUR8") (pin "1") (pinfunction "1_1") (pintype "passive"))
      (node (ref "SER8") (pin "2") (pinfunction "2_2") (pintype "passive"))
      (node (ref "X3") (pin "8") (pinfunction "1_8") (pintype "passive"))
    )
    (net (code "103") (name "unconnected-(U$2-P$8-Pad8)") (class "Default")
      (node (ref "U$2") (pin "8") (pinfunction "P$8_8") (pintype "bidirectional"))
    )
    (net (code "104") (name "unconnected-(U$4-FT{slash}OUT-Pad7)") (class "Default")
      (node (ref "U$4") (pin "7") (pinfunction "FT/OUT_7") (pintype "bidirectional"))
    )
  )
)
